# EEZ_DIB_MCU_r1B6.net
KiCad netlist of a schematic drawn in EAGLE
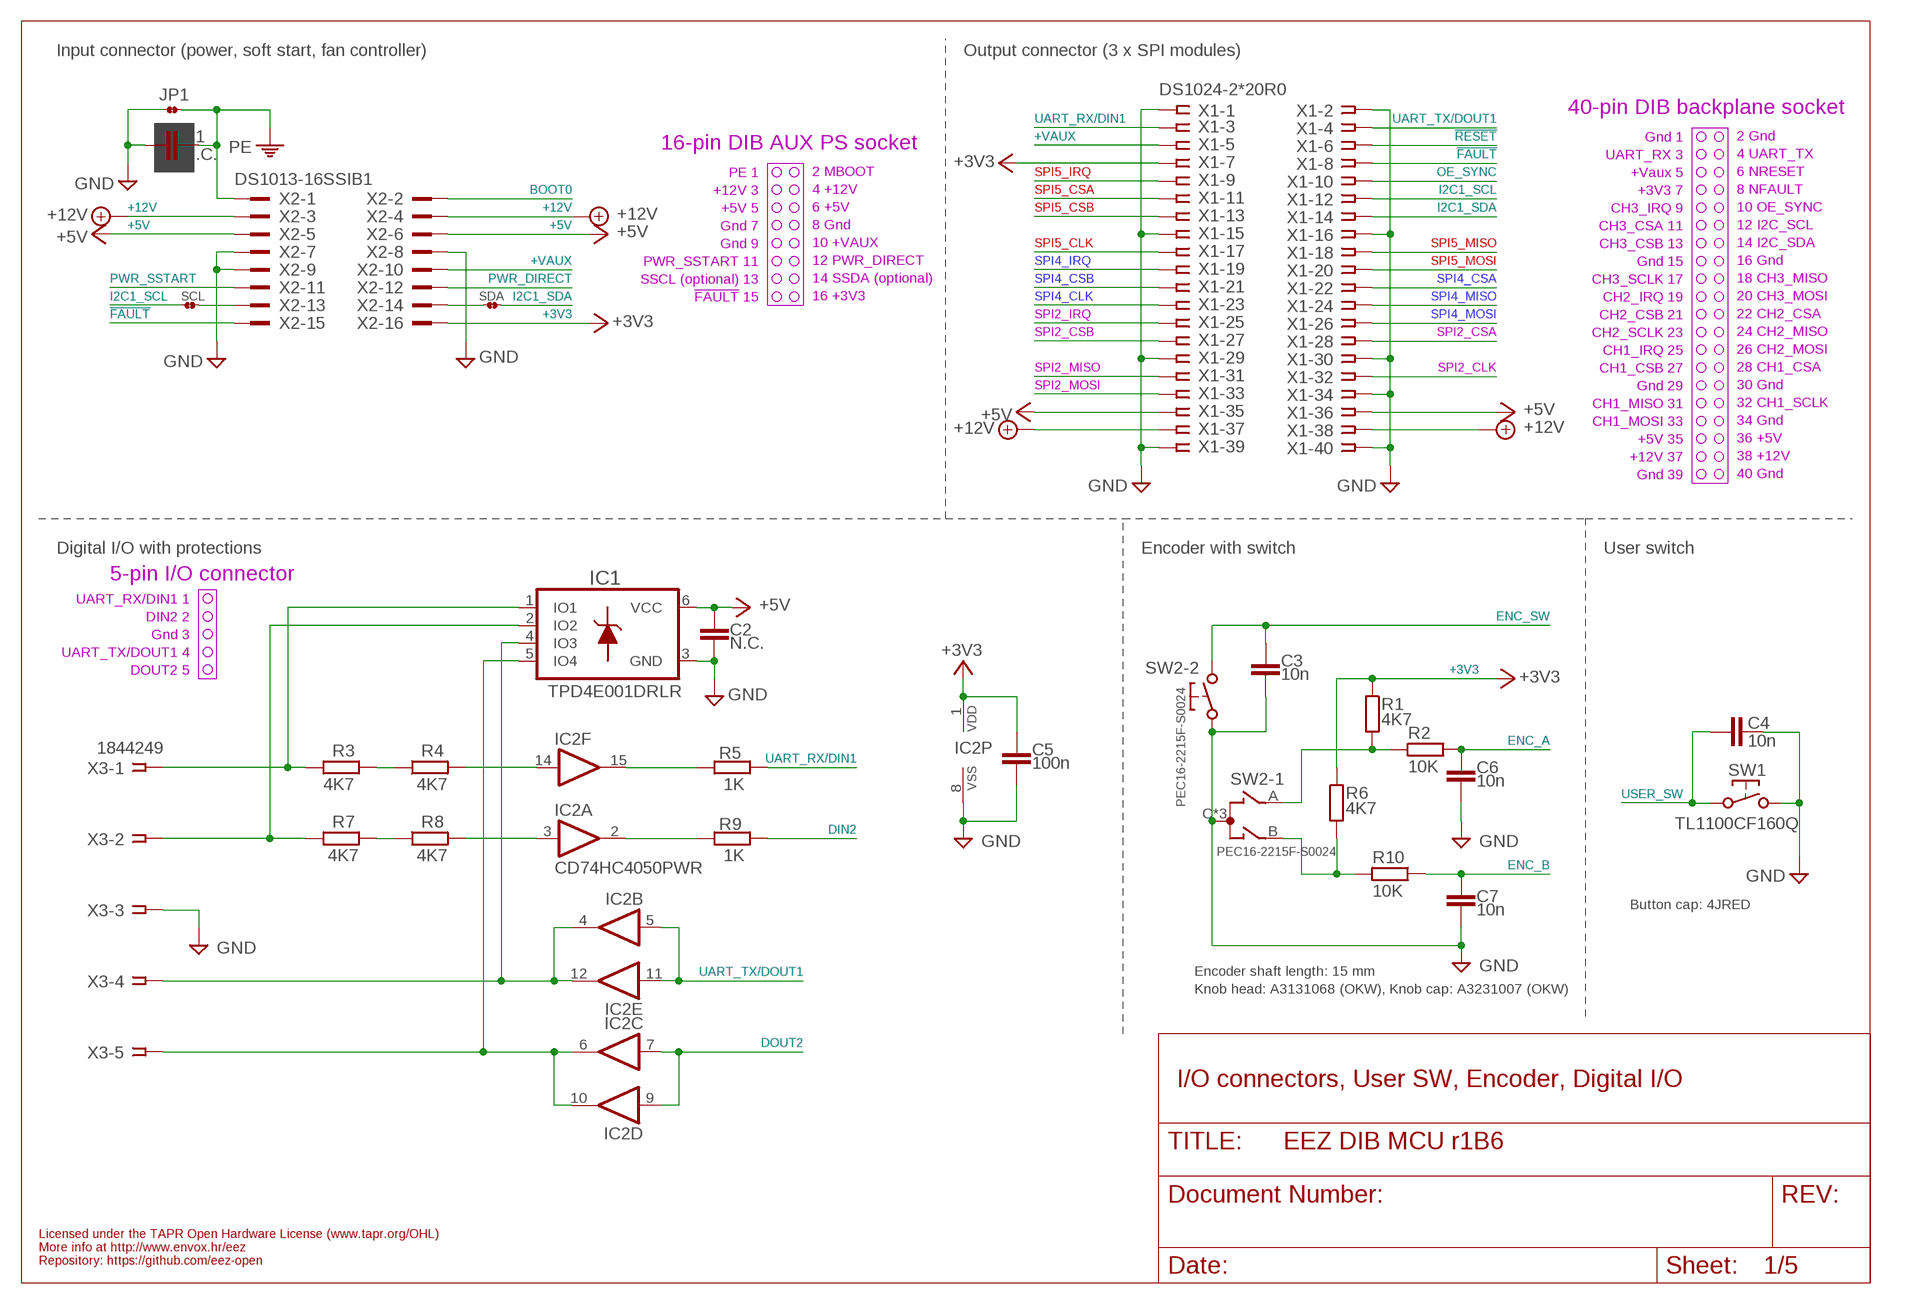
[diagram p0: schematic, sheet 1]
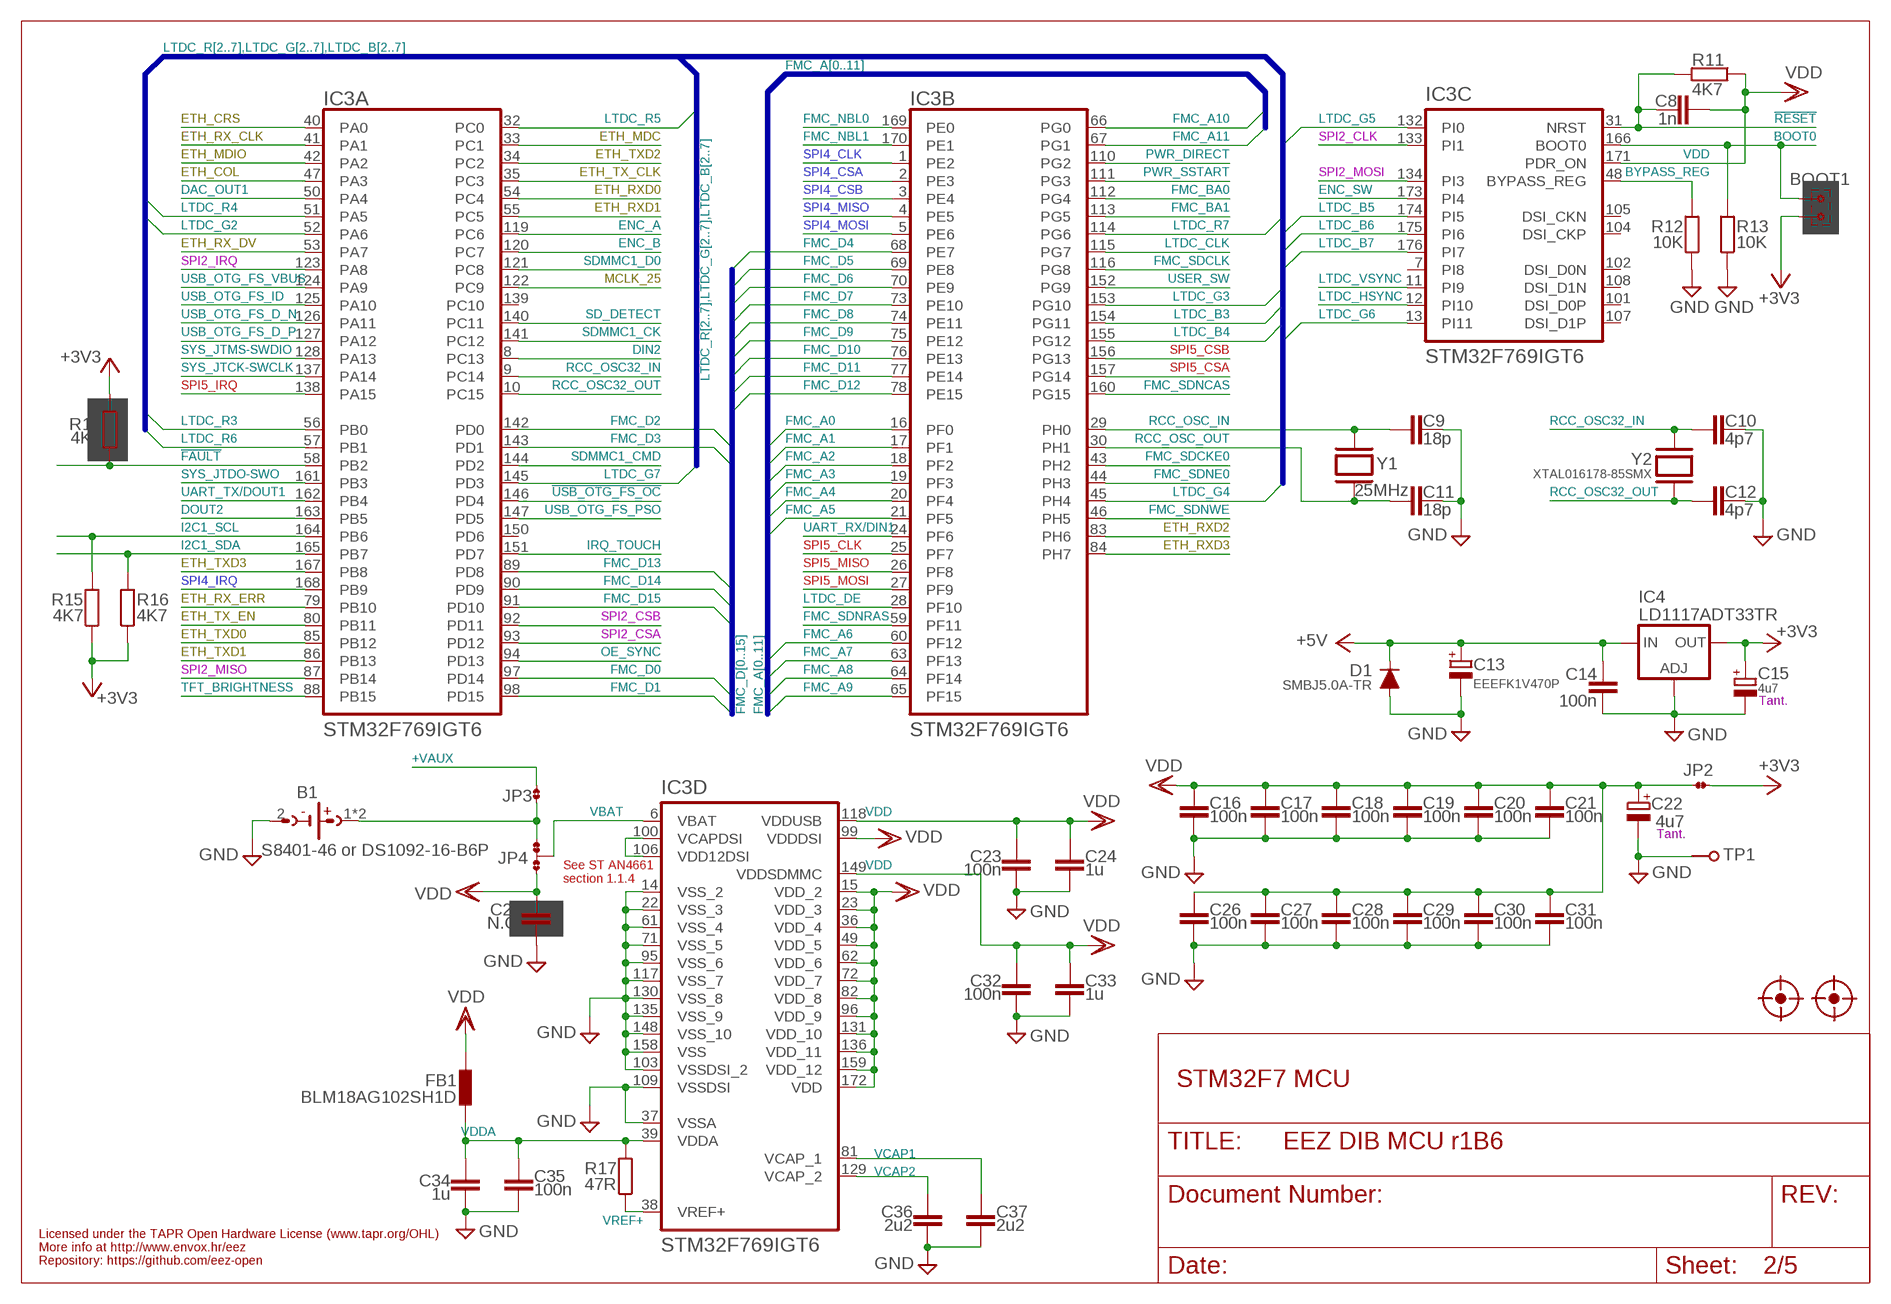
[diagram p1: schematic, sheet 2]
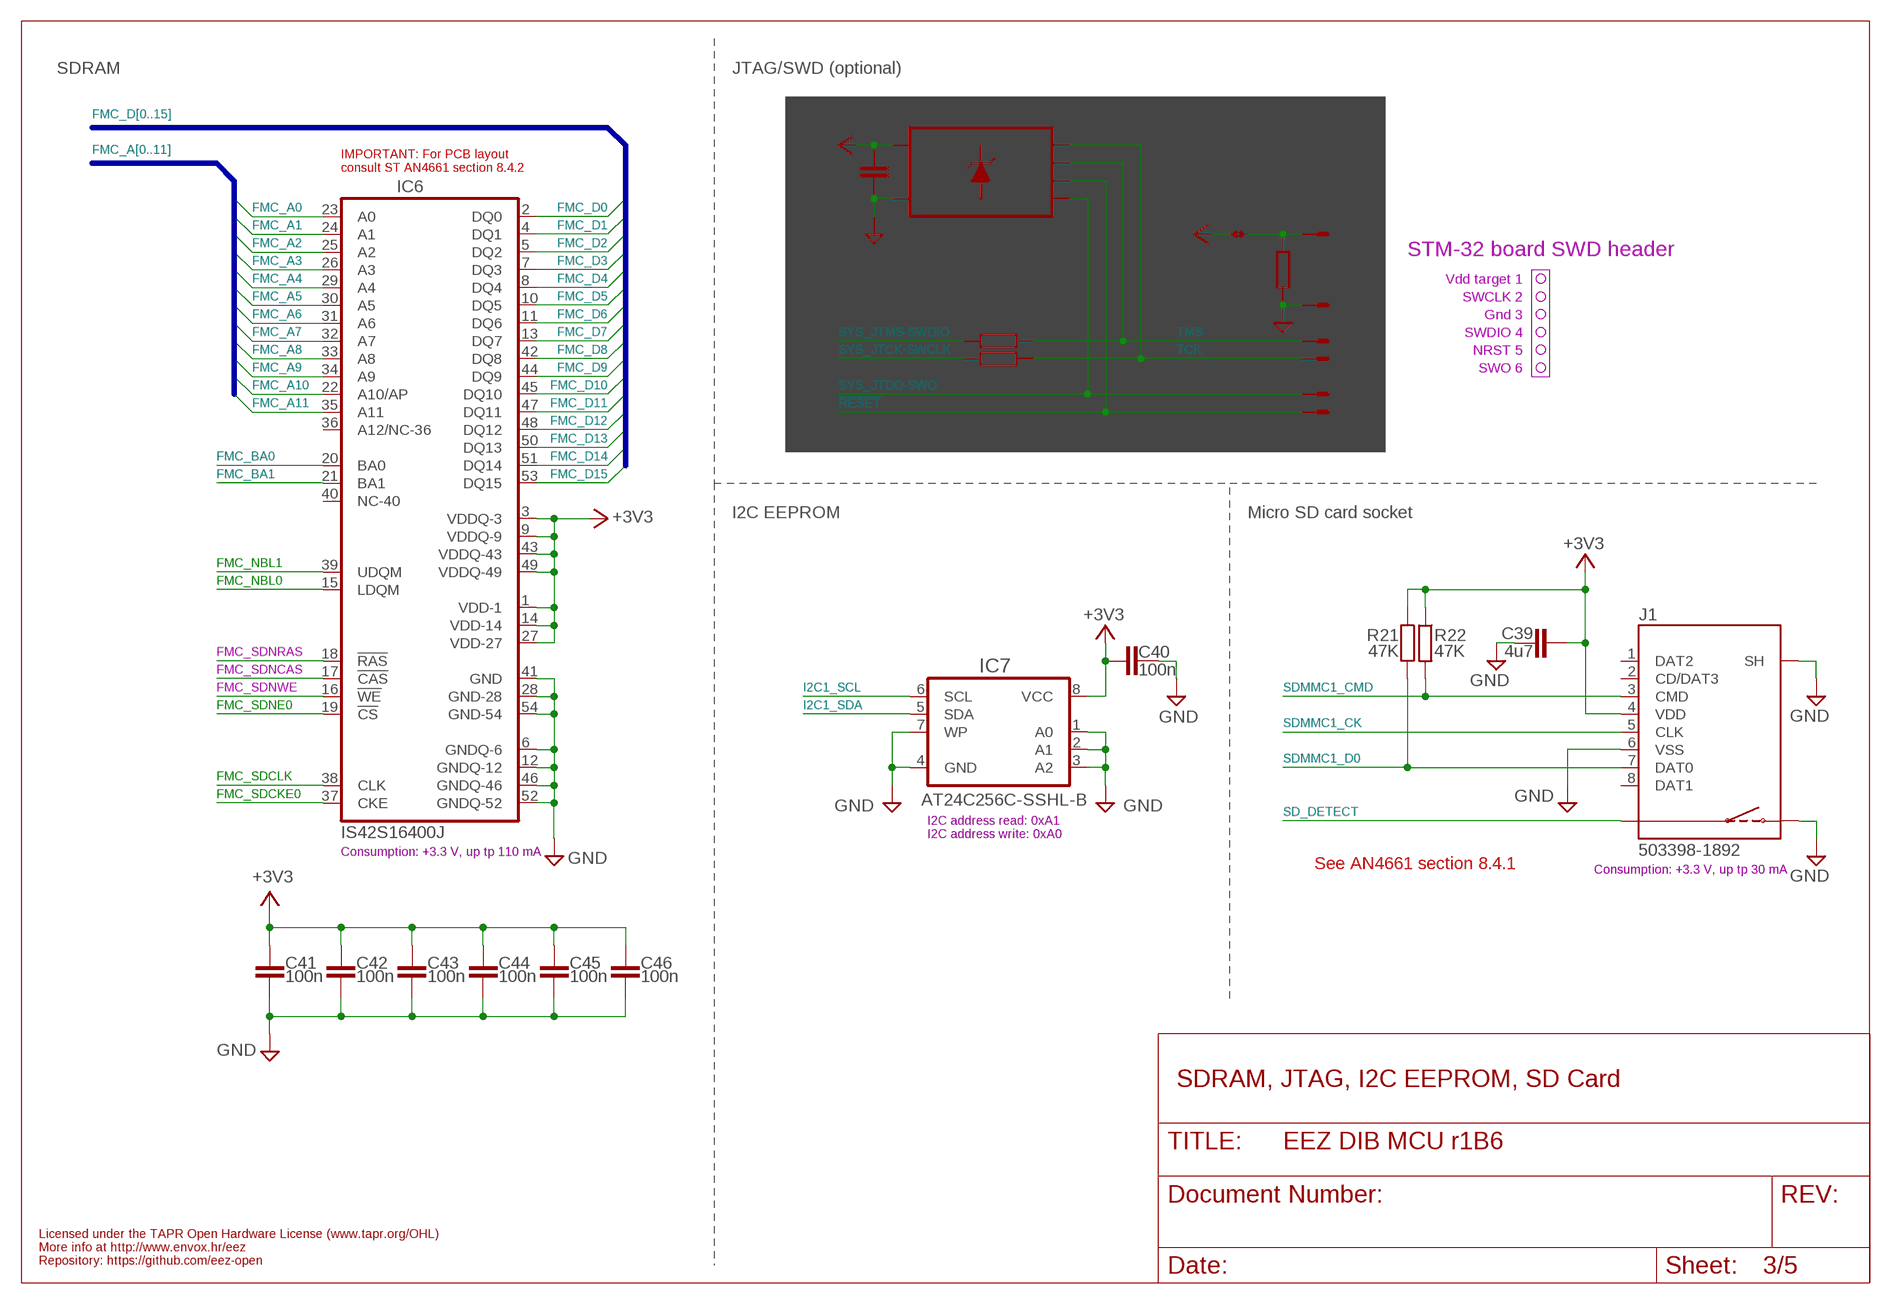
[diagram p2: schematic, sheet 3]
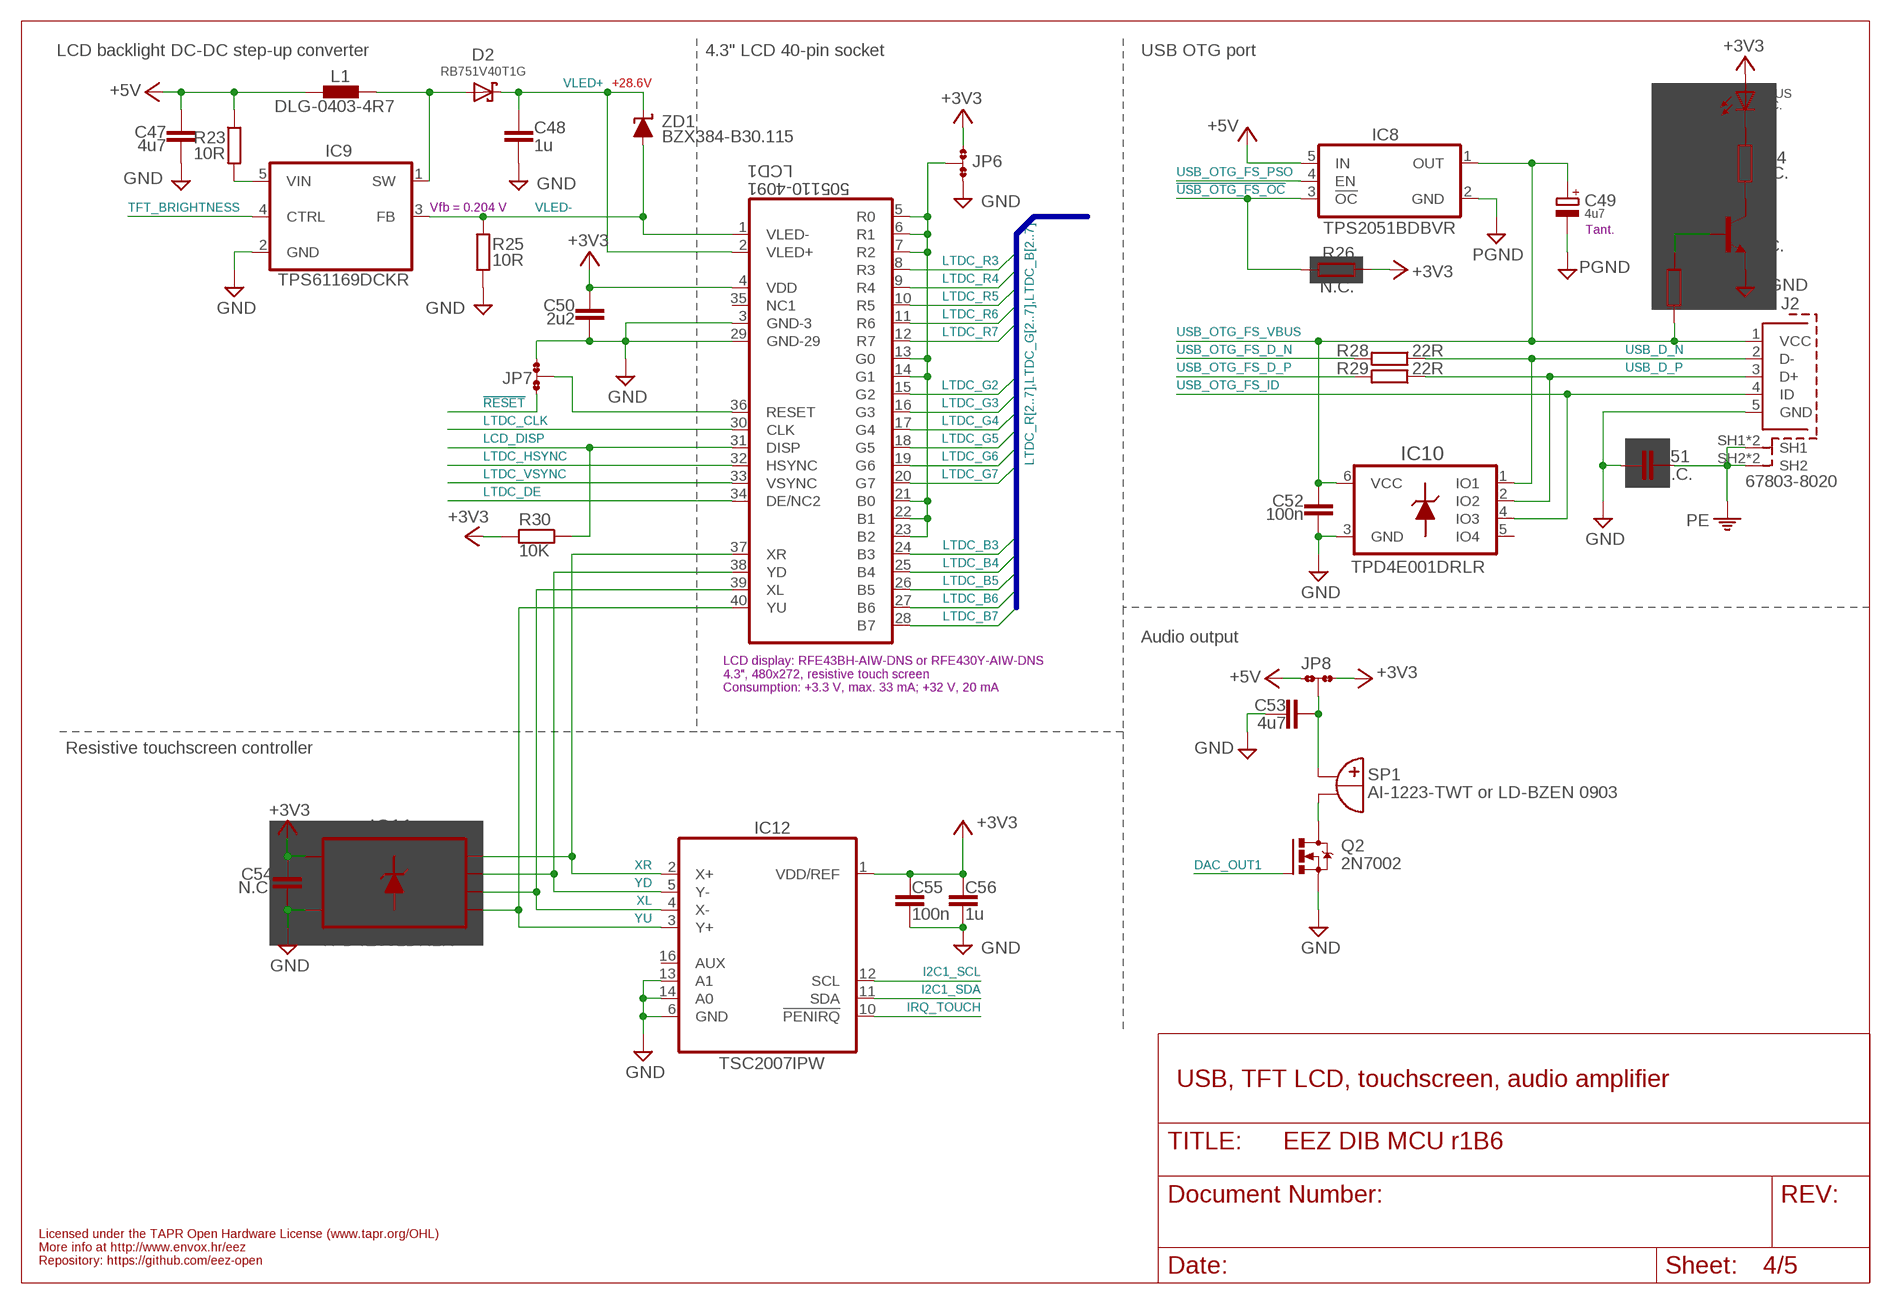
[diagram p3: schematic, sheet 4]
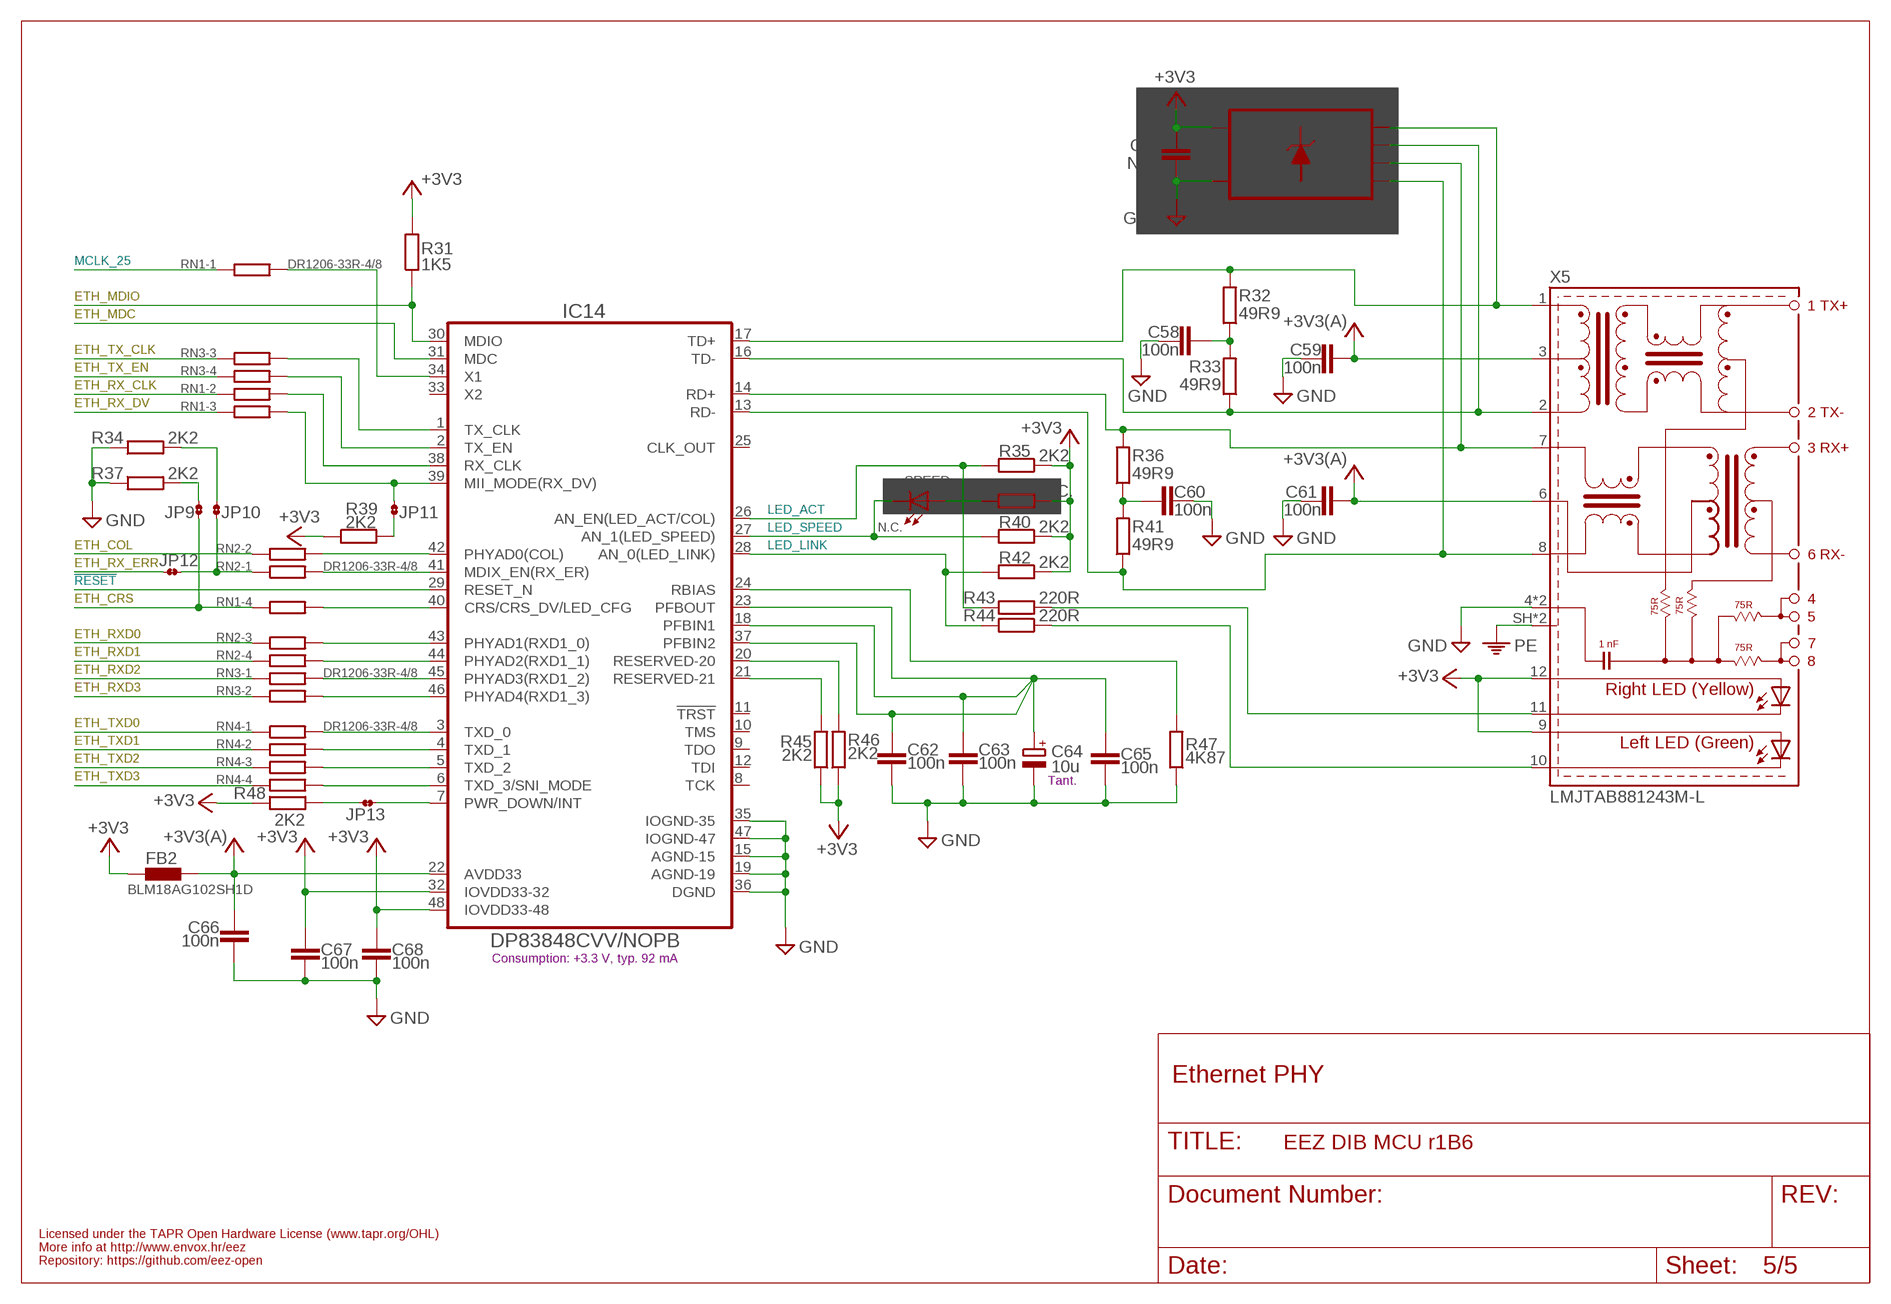
[diagram p4: schematic, sheet 5]

(export (version "E")
  (design (tool "Eeschema 10.0.6"))
  (components
    (comp (ref "B1")
      (value "S8401-46 or DS1092-16-B6P")
      (footprint "eagle-import:S8401-46")
      (libsource (lib "eagle-import") (part "CELL_BATTERYVERT"))
    )
    (comp (ref "BOOT1")
      (value "JUMPER-2PIN-2MM")
      (footprint "eagle-import:2MM-2")
      (libsource (lib "eagle-import") (part "JUMPER-2PIN-2MM"))
    )
    (comp (ref "C8")
      (value "1n")
      (footprint "eagle-import:C0805")
      (libsource (lib "eagle-import") (part "C-EUC0805"))
    )
    (comp (ref "C9")
      (value "18p")
      (footprint "eagle-import:C0603")
      (libsource (lib "eagle-import") (part "C-EUC0603"))
    )
    (comp (ref "C10")
      (value "4p7")
      (footprint "eagle-import:C0603")
      (libsource (lib "eagle-import") (part "C-EUC0603"))
    )
    (comp (ref "C11")
      (value "18p")
      (footprint "eagle-import:C0603")
      (libsource (lib "eagle-import") (part "C-EUC0603"))
    )
    (comp (ref "C12")
      (value "4p7")
      (footprint "eagle-import:C0603")
      (libsource (lib "eagle-import") (part "C-EUC0603"))
    )
    (comp (ref "C13")
      (value "EEEFK1V470P")
      (footprint "eagle-import:CAPAE660X610N")
      (libsource (lib "eagle-import") (part "ECAPPANASONIC_H"))
    )
    (comp (ref "C14")
      (value "100n")
      (footprint "eagle-import:C0603")
      (libsource (lib "eagle-import") (part "C-EUC0603"))
    )
    (comp (ref "C15")
      (value "4u7")
      (footprint "eagle-import:EC1206")
      (libsource (lib "eagle-import") (part "ECAP1206"))
    )
    (comp (ref "C16")
      (value "100n")
      (footprint "eagle-import:C0603")
      (libsource (lib "eagle-import") (part "C-EUC0603"))
    )
    (comp (ref "C17")
      (value "100n")
      (footprint "eagle-import:C0603")
      (libsource (lib "eagle-import") (part "C-EUC0603"))
    )
    (comp (ref "C18")
      (value "100n")
      (footprint "eagle-import:C0603")
      (libsource (lib "eagle-import") (part "C-EUC0603"))
    )
    (comp (ref "C19")
      (value "100n")
      (footprint "eagle-import:C0603")
      (libsource (lib "eagle-import") (part "C-EUC0603"))
    )
    (comp (ref "C20")
      (value "100n")
      (footprint "eagle-import:C0603")
      (libsource (lib "eagle-import") (part "C-EUC0603"))
    )
    (comp (ref "C21")
      (value "100n")
      (footprint "eagle-import:C0603")
      (libsource (lib "eagle-import") (part "C-EUC0603"))
    )
    (comp (ref "C22")
      (value "4u7")
      (footprint "eagle-import:EC1206")
      (libsource (lib "eagle-import") (part "ECAP1206"))
    )
    (comp (ref "C23")
      (value "100n")
      (footprint "eagle-import:C0603")
      (libsource (lib "eagle-import") (part "C-EUC0603"))
    )
    (comp (ref "C24")
      (value "1u")
      (footprint "eagle-import:C0805")
      (libsource (lib "eagle-import") (part "C-EUC0805"))
    )
    (comp (ref "C25")
      (value "N.C.")
      (footprint "eagle-import:C0603")
      (libsource (lib "eagle-import") (part "C-EUC0603"))
    )
    (comp (ref "C26")
      (value "100n")
      (footprint "eagle-import:C0603")
      (libsource (lib "eagle-import") (part "C-EUC0603"))
    )
    (comp (ref "C27")
      (value "100n")
      (footprint "eagle-import:C0603")
      (libsource (lib "eagle-import") (part "C-EUC0603"))
    )
    (comp (ref "C28")
      (value "100n")
      (footprint "eagle-import:C0603")
      (libsource (lib "eagle-import") (part "C-EUC0603"))
    )
    (comp (ref "C29")
      (value "100n")
      (footprint "eagle-import:C0603")
      (libsource (lib "eagle-import") (part "C-EUC0603"))
    )
    (comp (ref "C30")
      (value "100n")
      (footprint "eagle-import:C0603")
      (libsource (lib "eagle-import") (part "C-EUC0603"))
    )
    (comp (ref "C31")
      (value "100n")
      (footprint "eagle-import:C0603")
      (libsource (lib "eagle-import") (part "C-EUC0603"))
    )
    (comp (ref "C32")
      (value "100n")
      (footprint "eagle-import:C0603")
      (libsource (lib "eagle-import") (part "C-EUC0603"))
    )
    (comp (ref "C33")
      (value "1u")
      (footprint "eagle-import:C0805")
      (libsource (lib "eagle-import") (part "C-EUC0805"))
    )
    (comp (ref "C34")
      (value "1u")
      (footprint "eagle-import:C0805")
      (libsource (lib "eagle-import") (part "C-EUC0805"))
    )
    (comp (ref "C35")
      (value "100n")
      (footprint "eagle-import:C0603")
      (libsource (lib "eagle-import") (part "C-EUC0603"))
    )
    (comp (ref "C36")
      (value "2u2")
      (footprint "eagle-import:C0805")
      (libsource (lib "eagle-import") (part "C-EUC0805"))
    )
    (comp (ref "C37")
      (value "2u2")
      (footprint "eagle-import:C0805")
      (libsource (lib "eagle-import") (part "C-EUC0805"))
    )
    (comp (ref "D1")
      (value "SMBJ5.0A-TR")
      (footprint "eagle-import:DO214AA")
      (libsource (lib "eagle-import") (part "DIODEDO214AA"))
    )
    (comp (ref "FB1")
      (value "BLM18AG102SH1D")
      (footprint "eagle-import:BEAD0603")
      (libsource (lib "eagle-import") (part "FERRITE_BEAD0603"))
    )
    (comp (ref "FM1")
      (value "FIDUCIAL")
      (footprint "eagle-import:FIDUCIAL")
      (libsource (lib "eagle-import") (part "FIDUCIAL"))
    )
    (comp (ref "FM2")
      (value "FIDUCIAL")
      (footprint "eagle-import:FIDUCIAL")
      (libsource (lib "eagle-import") (part "FIDUCIAL"))
    )
    (comp (ref "IC3")
      (value "STM32F769IGT6")
      (footprint "eagle-import:LQFP-176_24X24MM")
      (fields
        (field (name "MANUFACTURER_PART_NUMBER") "stm32f769ixt")
        (field (name "COPYRIGHT") "Copyright C 2016 Accelerated Designs. All rights reserved")
      )
      (libsource (lib "eagle-import") (part "STM32F769IXT"))
    )
    (comp (ref "IC4")
      (value "LD1117ADT33TR")
      (footprint "eagle-import:DPACK")
      (libsource (lib "eagle-import") (part "LD117A?DT33TR"))
    )
    (comp (ref "JP2")
      (value "JP2-NOCUT")
      (footprint "eagle-import:JP2-NOCUT")
      (libsource (lib "eagle-import") (part "JP2-NOCUT"))
    )
    (comp (ref "JP3")
      (value "JP2-CUT")
      (footprint "eagle-import:JP2-CUT")
      (libsource (lib "eagle-import") (part "JP2-CUT"))
    )
    (comp (ref "JP4")
      (value "JP3-CUT")
      (footprint "eagle-import:JP3-CUT")
      (libsource (lib "eagle-import") (part "JP3-CUT"))
    )
    (comp (ref "R11")
      (value "4K7")
      (footprint "eagle-import:R0805")
      (libsource (lib "eagle-import") (part "R-EU_R0805"))
    )
    (comp (ref "R12")
      (value "10K")
      (footprint "eagle-import:R0805")
      (libsource (lib "eagle-import") (part "R-EU_R0805"))
    )
    (comp (ref "R13")
      (value "10K")
      (footprint "eagle-import:R0805")
      (libsource (lib "eagle-import") (part "R-EU_R0805"))
    )
    (comp (ref "R14")
      (value "4K7")
      (footprint "eagle-import:R0805")
      (libsource (lib "eagle-import") (part "R-EU_R0805"))
    )
    (comp (ref "R15")
      (value "4K7")
      (footprint "eagle-import:R0805")
      (libsource (lib "eagle-import") (part "R-EU_R0805"))
    )
    (comp (ref "R16")
      (value "4K7")
      (footprint "eagle-import:R0805")
      (libsource (lib "eagle-import") (part "R-EU_R0805"))
    )
    (comp (ref "R17")
      (value "47R")
      (footprint "eagle-import:R0805")
      (libsource (lib "eagle-import") (part "R-EU_R0805"))
    )
    (comp (ref "TP1")
      (value "PCB_TEST_TABSHIELD")
      (footprint "eagle-import:PCB_SHIELD_TAB")
      (libsource (lib "eagle-import") (part "PCB_TEST_TABSHIELD"))
    )
    (comp (ref "Y1")
      (value "25MHz")
      (footprint "eagle-import:HC-49_4H")
      (libsource (lib "eagle-import") (part "XTALSMD"))
    )
    (comp (ref "Y2")
      (value "XTAL016178-85SMX")
      (footprint "eagle-import:85SMX")
      (libsource (lib "eagle-import") (part "XTAL85SMX"))
    )
    (comp (ref "C38")
      (value "N.C.")
      (footprint "eagle-import:C0603")
      (libsource (lib "eagle-import") (part "C-EUC0603"))
    )
    (comp (ref "C39")
      (value "4u7")
      (footprint "eagle-import:C1206")
      (libsource (lib "eagle-import") (part "C-EUC1206"))
    )
    (comp (ref "C40")
      (value "100n")
      (footprint "eagle-import:C0603")
      (libsource (lib "eagle-import") (part "C-EUC0603"))
    )
    (comp (ref "C41")
      (value "100n")
      (footprint "eagle-import:C0603")
      (libsource (lib "eagle-import") (part "C-EUC0603"))
    )
    (comp (ref "C42")
      (value "100n")
      (footprint "eagle-import:C0603")
      (libsource (lib "eagle-import") (part "C-EUC0603"))
    )
    (comp (ref "C43")
      (value "100n")
      (footprint "eagle-import:C0603")
      (libsource (lib "eagle-import") (part "C-EUC0603"))
    )
    (comp (ref "C44")
      (value "100n")
      (footprint "eagle-import:C0603")
      (libsource (lib "eagle-import") (part "C-EUC0603"))
    )
    (comp (ref "C45")
      (value "100n")
      (footprint "eagle-import:C0603")
      (libsource (lib "eagle-import") (part "C-EUC0603"))
    )
    (comp (ref "C46")
      (value "100n")
      (footprint "eagle-import:C0603")
      (libsource (lib "eagle-import") (part "C-EUC0603"))
    )
    (comp (ref "IC5")
      (value "TPD4E001DRLR")
      (footprint "eagle-import:DRL6")
      (libsource (lib "eagle-import") (part "TPD4E001-DRL"))
    )
    (comp (ref "IC6")
      (value "IS42S16400J")
      (footprint "eagle-import:TSOPII-54")
      (libsource (lib "eagle-import") (part "IS42S16400"))
    )
    (comp (ref "IC7")
      (value "AT24C256C-SSHL-B")
      (footprint "eagle-import:SOIC127P600X173-8N")
      (libsource (lib "eagle-import") (part "AT24CXXSOIC8"))
    )
    (comp (ref "J1")
      (value "503398-1892")
      (footprint "eagle-import:5033981892")
      (libsource (lib "eagle-import") (part "5033981892"))
    )
    (comp (ref "JP5")
      (value "JP2-CUT")
      (footprint "eagle-import:JP2-CUT")
      (libsource (lib "eagle-import") (part "JP2-CUT"))
    )
    (comp (ref "R18")
      (value "N.C.")
      (footprint "eagle-import:R0805")
      (libsource (lib "eagle-import") (part "R-EU_R0805"))
    )
    (comp (ref "R19")
      (value "N.C.")
      (footprint "eagle-import:R0805")
      (libsource (lib "eagle-import") (part "R-EU_R0805"))
    )
    (comp (ref "R20")
      (value "N.C.")
      (footprint "eagle-import:R0805")
      (libsource (lib "eagle-import") (part "R-EU_R0805"))
    )
    (comp (ref "R21")
      (value "47K")
      (footprint "eagle-import:R0805")
      (libsource (lib "eagle-import") (part "R-EU_R0805"))
    )
    (comp (ref "R22")
      (value "47K")
      (footprint "eagle-import:R0805")
      (libsource (lib "eagle-import") (part "R-EU_R0805"))
    )
    (comp (ref "X4")
      (value "N.C.")
      (footprint "eagle-import:22-23-2061")
      (fields (field (name "MF") "MOLEX") (field (name "MPN") "22-23-2061"))
      (libsource (lib "eagle-import") (part "22-23-2061"))
    )
    (comp (ref "C47")
      (value "4u7")
      (footprint "eagle-import:C1206")
      (libsource (lib "eagle-import") (part "C-EUC1206"))
    )
    (comp (ref "C48")
      (value "1u")
      (footprint "eagle-import:C0805")
      (libsource (lib "eagle-import") (part "C-EUC0805"))
    )
    (comp (ref "C49")
      (value "4u7")
      (footprint "eagle-import:EC1206")
      (libsource (lib "eagle-import") (part "ECAP1206"))
    )
    (comp (ref "C50")
      (value "2u2")
      (footprint "eagle-import:C0805")
      (libsource (lib "eagle-import") (part "C-EUC0805"))
    )
    (comp (ref "C51")
      (value "N.C.")
      (footprint "eagle-import:C0805")
      (libsource (lib "eagle-import") (part "C-EUC0805"))
    )
    (comp (ref "C52")
      (value "100n")
      (footprint "eagle-import:C0603")
      (libsource (lib "eagle-import") (part "C-EUC0603"))
    )
    (comp (ref "C53")
      (value "4u7")
      (footprint "eagle-import:C1206")
      (libsource (lib "eagle-import") (part "C-EUC1206"))
    )
    (comp (ref "C54")
      (value "N.C.")
      (footprint "eagle-import:C0603")
      (libsource (lib "eagle-import") (part "C-EUC0603"))
    )
    (comp (ref "C55")
      (value "100n")
      (footprint "eagle-import:C0603")
      (libsource (lib "eagle-import") (part "C-EUC0603"))
    )
    (comp (ref "C56")
      (value "1u")
      (footprint "eagle-import:C0805")
      (libsource (lib "eagle-import") (part "C-EUC0805"))
    )
    (comp (ref "D2")
      (value "RB751V40T1G")
      (footprint "eagle-import:SOD323-R")
      (libsource (lib "eagle-import") (part "SCHOTTKYSOD-323R"))
    )
    (comp (ref "IC8")
      (value "TPS2051BDBVR")
      (footprint "eagle-import:DBV5")
      (libsource (lib "eagle-import") (part "TPS2051B"))
    )
    (comp (ref "IC9")
      (value "TPS61169DCKR")
      (footprint "eagle-import:DCK5")
      (fields (field (name "MANUFACTURER") "Texas Instruments"))
      (libsource (lib "eagle-import") (part "TPS61169DCKR"))
    )
    (comp (ref "IC10")
      (value "TPD4E001DRLR")
      (footprint "eagle-import:DRL6")
      (libsource (lib "eagle-import") (part "TPD4E001-DRL"))
    )
    (comp (ref "IC11")
      (value "TPD4E001DRLR")
      (footprint "eagle-import:DRL6")
      (libsource (lib "eagle-import") (part "TPD4E001-DRL"))
    )
    (comp (ref "IC12")
      (value "TSC2007IPW")
      (footprint "eagle-import:PW(R-PDSO-G16)")
      (libsource (lib "eagle-import") (part "TSC2007IPW"))
    )
    (comp (ref "J2")
      (value "67803-8020")
      (footprint "eagle-import:678038020")
      (libsource (lib "eagle-import") (part "678038020"))
    )
    (comp (ref "JP6")
      (value "JP3-CUT")
      (footprint "eagle-import:JP3-CUT")
      (libsource (lib "eagle-import") (part "JP3-CUT"))
    )
    (comp (ref "JP7")
      (value "JP3-CUT")
      (footprint "eagle-import:JP3-CUT")
      (libsource (lib "eagle-import") (part "JP3-CUT"))
    )
    (comp (ref "JP8")
      (value "JP3-CUT")
      (footprint "eagle-import:JP3-CUT")
      (libsource (lib "eagle-import") (part "JP3-CUT"))
    )
    (comp (ref "L1")
      (value "DLG-0403-4R7")
      (footprint "eagle-import:DE0403")
      (libsource (lib "eagle-import") (part "DE0403"))
    )
    (comp (ref "LCD1")
      (value "505110-4091")
      (footprint "eagle-import:FPC_40")
      (libsource (lib "eagle-import") (part "RFE430Y-AIW-DNS"))
    )
    (comp (ref "Q1")
      (value "N.C.")
      (footprint "eagle-import:SOT23-BEC")
      (libsource (lib "eagle-import") (part "-NPN-SOT23-BECMMBT5551LT1"))
    )
    (comp (ref "Q2")
      (value "2N7002")
      (footprint "eagle-import:SOT103P240X110-3N")
      (fields (field (name "MPN") "2N7002-7-F"))
      (libsource (lib "eagle-import") (part "2N7002"))
    )
    (comp (ref "R23")
      (value "10R")
      (footprint "eagle-import:R0805")
      (libsource (lib "eagle-import") (part "R-EU_R0805"))
    )
    (comp (ref "R24")
      (value "N.C.")
      (footprint "eagle-import:R0805")
      (libsource (lib "eagle-import") (part "R-EU_R0805"))
    )
    (comp (ref "R25")
      (value "10R")
      (footprint "eagle-import:R0805")
      (libsource (lib "eagle-import") (part "R-EU_R0805"))
    )
    (comp (ref "R26")
      (value "N.C.")
      (footprint "eagle-import:R0805")
      (libsource (lib "eagle-import") (part "R-EU_R0805"))
    )
    (comp (ref "R27")
      (value "N.C.")
      (footprint "eagle-import:R0805")
      (libsource (lib "eagle-import") (part "R-EU_R0805"))
    )
    (comp (ref "R28")
      (value "22R")
      (footprint "eagle-import:R0805")
      (libsource (lib "eagle-import") (part "R-EU_R0805"))
    )
    (comp (ref "R29")
      (value "22R")
      (footprint "eagle-import:R0805")
      (libsource (lib "eagle-import") (part "R-EU_R0805"))
    )
    (comp (ref "R30")
      (value "10K")
      (footprint "eagle-import:R0805")
      (libsource (lib "eagle-import") (part "R-EU_R0805"))
    )
    (comp (ref "SP1")
      (value "AI-1223-TWT or LD-BZEN 0903")
      (footprint "eagle-import:AI-1223-TWT_COMBO")
      (libsource (lib "eagle-import") (part "AI-1223-TWT-LDB0903"))
    )
    (comp (ref "VBUS")
      (value "N.C.")
      (footprint "eagle-import:LED_0805")
      (libsource (lib "eagle-import") (part "LED0805"))
    )
    (comp (ref "ZD1")
      (value "BZX384-B30.115")
      (footprint "eagle-import:SOD323-W")
      (libsource (lib "eagle-import") (part "ZENER-DIODESOD323"))
    )
    (comp (ref "C57")
      (value "N.C.")
      (footprint "eagle-import:C0603")
      (libsource (lib "eagle-import") (part "C-EUC0603"))
    )
    (comp (ref "C58")
      (value "100n")
      (footprint "eagle-import:C0603")
      (libsource (lib "eagle-import") (part "C-EUC0603"))
    )
    (comp (ref "C59")
      (value "100n")
      (footprint "eagle-import:C0603")
      (libsource (lib "eagle-import") (part "C-EUC0603"))
    )
    (comp (ref "C60")
      (value "100n")
      (footprint "eagle-import:C0603")
      (libsource (lib "eagle-import") (part "C-EUC0603"))
    )
    (comp (ref "C61")
      (value "100n")
      (footprint "eagle-import:C0603")
      (libsource (lib "eagle-import") (part "C-EUC0603"))
    )
    (comp (ref "C62")
      (value "100n")
      (footprint "eagle-import:C0603")
      (libsource (lib "eagle-import") (part "C-EUC0603"))
    )
    (comp (ref "C63")
      (value "100n")
      (footprint "eagle-import:C0603")
      (libsource (lib "eagle-import") (part "C-EUC0603"))
    )
    (comp (ref "C64")
      (value "10u")
      (footprint "eagle-import:EC1206")
      (libsource (lib "eagle-import") (part "ECAP1206"))
    )
    (comp (ref "C65")
      (value "100n")
      (footprint "eagle-import:C0603")
      (libsource (lib "eagle-import") (part "C-EUC0603"))
    )
    (comp (ref "C66")
      (value "100n")
      (footprint "eagle-import:C0603")
      (libsource (lib "eagle-import") (part "C-EUC0603"))
    )
    (comp (ref "C67")
      (value "100n")
      (footprint "eagle-import:C0603")
      (libsource (lib "eagle-import") (part "C-EUC0603"))
    )
    (comp (ref "C68")
      (value "100n")
      (footprint "eagle-import:C0603")
      (libsource (lib "eagle-import") (part "C-EUC0603"))
    )
    (comp (ref "FB2")
      (value "BLM18AG102SH1D")
      (footprint "eagle-import:BEAD0603")
      (libsource (lib "eagle-import") (part "FERRITE_BEAD0603"))
    )
    (comp (ref "IC13")
      (value "TPD4E001DRLR")
      (footprint "eagle-import:DRL6")
      (libsource (lib "eagle-import") (part "TPD4E001-DRL"))
    )
    (comp (ref "IC14")
      (value "DP83848CVV/NOPB")
      (footprint "eagle-import:PT48")
      (libsource (lib "eagle-import") (part "DP83848CVV/NOPB"))
    )
    (comp (ref "JP9")
      (value "JP2-CUT")
      (footprint "eagle-import:JP2-CUT")
      (libsource (lib "eagle-import") (part "JP2-CUT"))
    )
    (comp (ref "JP10")
      (value "JP2-CUT")
      (footprint "eagle-import:JP2-CUT")
      (libsource (lib "eagle-import") (part "JP2-CUT"))
    )
    (comp (ref "JP11")
      (value "JP2-CUT")
      (footprint "eagle-import:JP2-CUT")
      (libsource (lib "eagle-import") (part "JP2-CUT"))
    )
    (comp (ref "JP12")
      (value "JP2-NOCUT")
      (footprint "eagle-import:JP2-NOCUT")
      (libsource (lib "eagle-import") (part "JP2-NOCUT"))
    )
    (comp (ref "JP13")
      (value "JP2-NOCUT")
      (footprint "eagle-import:JP2-NOCUT")
      (libsource (lib "eagle-import") (part "JP2-NOCUT"))
    )
    (comp (ref "R31")
      (value "1K5")
      (footprint "eagle-import:R0805")
      (libsource (lib "eagle-import") (part "R-EU_R0805"))
    )
    (comp (ref "R32")
      (value "49R9")
      (footprint "eagle-import:R0805")
      (libsource (lib "eagle-import") (part "R-EU_R0805"))
    )
    (comp (ref "R33")
      (value "49R9")
      (footprint "eagle-import:R0805")
      (libsource (lib "eagle-import") (part "R-EU_R0805"))
    )
    (comp (ref "R34")
      (value "2K2")
      (footprint "eagle-import:R0805")
      (libsource (lib "eagle-import") (part "R-EU_R0805"))
    )
    (comp (ref "R35")
      (value "2K2")
      (footprint "eagle-import:R0805")
      (libsource (lib "eagle-import") (part "R-EU_R0805"))
    )
    (comp (ref "R36")
      (value "49R9")
      (footprint "eagle-import:R0805")
      (libsource (lib "eagle-import") (part "R-EU_R0805"))
    )
    (comp (ref "R37")
      (value "2K2")
      (footprint "eagle-import:R0805")
      (libsource (lib "eagle-import") (part "R-EU_R0805"))
    )
    (comp (ref "R38")
      (value "N.C.")
      (footprint "eagle-import:R0805")
      (libsource (lib "eagle-import") (part "R-EU_R0805"))
    )
    (comp (ref "R39")
      (value "2K2")
      (footprint "eagle-import:R0805")
      (libsource (lib "eagle-import") (part "R-EU_R0805"))
    )
    (comp (ref "R40")
      (value "2K2")
      (footprint "eagle-import:R0805")
      (libsource (lib "eagle-import") (part "R-EU_R0805"))
    )
    (comp (ref "R41")
      (value "49R9")
      (footprint "eagle-import:R0805")
      (libsource (lib "eagle-import") (part "R-EU_R0805"))
    )
    (comp (ref "R42")
      (value "2K2")
      (footprint "eagle-import:R0805")
      (libsource (lib "eagle-import") (part "R-EU_R0805"))
    )
    (comp (ref "R43")
      (value "220R")
      (footprint "eagle-import:R0805")
      (libsource (lib "eagle-import") (part "R-EU_R0805"))
    )
    (comp (ref "R44")
      (value "220R")
      (footprint "eagle-import:R0805")
      (libsource (lib "eagle-import") (part "R-EU_R0805"))
    )
    (comp (ref "R45")
      (value "2K2")
      (footprint "eagle-import:R0805")
      (libsource (lib "eagle-import") (part "R-EU_R0805"))
    )
    (comp (ref "R46")
      (value "2K2")
      (footprint "eagle-import:R0805")
      (libsource (lib "eagle-import") (part "R-EU_R0805"))
    )
    (comp (ref "R47")
      (value "4K87")
      (footprint "eagle-import:R0805")
      (libsource (lib "eagle-import") (part "R-EU_R0805"))
    )
    (comp (ref "R48")
      (value "2K2")
      (footprint "eagle-import:R0805")
      (libsource (lib "eagle-import") (part "R-EU_R0805"))
    )
    (comp (ref "RN1")
      (value "DR1206-33R-4/8")
      (footprint "eagle-import:CAY16")
      (libsource (lib "eagle-import") (part "R_ARRAY4"))
    )
    (comp (ref "RN2")
      (value "DR1206-33R-4/8")
      (footprint "eagle-import:CAY16")
      (libsource (lib "eagle-import") (part "R_ARRAY4"))
    )
    (comp (ref "RN3")
      (value "DR1206-33R-4/8")
      (footprint "eagle-import:CAY16")
      (libsource (lib "eagle-import") (part "R_ARRAY4"))
    )
    (comp (ref "RN4")
      (value "DR1206-33R-4/8")
      (footprint "eagle-import:CAY16")
      (libsource (lib "eagle-import") (part "R_ARRAY4"))
    )
    (comp (ref "SPEED")
      (value "N.C.")
      (footprint "eagle-import:LED_0805")
      (libsource (lib "eagle-import") (part "LED0805"))
    )
    (comp (ref "X5")
      (value "LMJTAB881243M-L")
      (footprint "eagle-import:RJ45-TRAFO-LED")
      (libsource (lib "eagle-import") (part "RJ45-TRAFO-LED"))
    )
    (comp (ref "C1")
      (value "N.C.")
      (footprint "eagle-import:C0805")
      (libsource (lib "eagle-import") (part "C-EUC0805"))
    )
    (comp (ref "C2")
      (value "N.C.")
      (footprint "eagle-import:C0603")
      (libsource (lib "eagle-import") (part "C-EUC0603"))
    )
    (comp (ref "C3")
      (value "10n")
      (footprint "eagle-import:C0805")
      (libsource (lib "eagle-import") (part "C-EUC0805"))
    )
    (comp (ref "C4")
      (value "10n")
      (footprint "eagle-import:C0805")
      (libsource (lib "eagle-import") (part "C-EUC0805"))
    )
    (comp (ref "C5")
      (value "100n")
      (footprint "eagle-import:C0603")
      (libsource (lib "eagle-import") (part "C-EUC0603"))
    )
    (comp (ref "C6")
      (value "10n")
      (footprint "eagle-import:C0805")
      (libsource (lib "eagle-import") (part "C-EUC0805"))
    )
    (comp (ref "C7")
      (value "10n")
      (footprint "eagle-import:C0805")
      (libsource (lib "eagle-import") (part "C-EUC0805"))
    )
    (comp (ref "IC1")
      (value "TPD4E001DRLR")
      (footprint "eagle-import:DRL6")
      (libsource (lib "eagle-import") (part "TPD4E001-DRL"))
    )
    (comp (ref "IC2")
      (value "CD74HC4050PWR")
      (footprint "eagle-import:PW16")
      (libsource (lib "eagle-import") (part "CD74HC4050PWR"))
    )
    (comp (ref "JP1")
      (value "JP2-NOCUT")
      (footprint "eagle-import:JP2-NOCUT")
      (libsource (lib "eagle-import") (part "JP2-NOCUT"))
    )
    (comp (ref "R1")
      (value "4K7")
      (footprint "eagle-import:R0805")
      (libsource (lib "eagle-import") (part "R-EU_R0805"))
    )
    (comp (ref "R2")
      (value "10K")
      (footprint "eagle-import:R0805")
      (libsource (lib "eagle-import") (part "R-EU_R0805"))
    )
    (comp (ref "R3")
      (value "4K7")
      (footprint "eagle-import:R0805")
      (libsource (lib "eagle-import") (part "R-EU_R0805"))
    )
    (comp (ref "R4")
      (value "4K7")
      (footprint "eagle-import:R0805")
      (libsource (lib "eagle-import") (part "R-EU_R0805"))
    )
    (comp (ref "R5")
      (value "1K")
      (footprint "eagle-import:R0805")
      (libsource (lib "eagle-import") (part "R-EU_R0805"))
    )
    (comp (ref "R6")
      (value "4K7")
      (footprint "eagle-import:R0805")
      (libsource (lib "eagle-import") (part "R-EU_R0805"))
    )
    (comp (ref "R7")
      (value "4K7")
      (footprint "eagle-import:R0805")
      (libsource (lib "eagle-import") (part "R-EU_R0805"))
    )
    (comp (ref "R8")
      (value "4K7")
      (footprint "eagle-import:R0805")
      (libsource (lib "eagle-import") (part "R-EU_R0805"))
    )
    (comp (ref "R9")
      (value "1K")
      (footprint "eagle-import:R0805")
      (libsource (lib "eagle-import") (part "R-EU_R0805"))
    )
    (comp (ref "R10")
      (value "10K")
      (footprint "eagle-import:R0805")
      (libsource (lib "eagle-import") (part "R-EU_R0805"))
    )
    (comp (ref "SCL")
      (value "JP2-NOCUT")
      (footprint "eagle-import:JP2-NOCUT")
      (libsource (lib "eagle-import") (part "JP2-NOCUT"))
    )
    (comp (ref "SDA")
      (value "JP2-NOCUT")
      (footprint "eagle-import:JP2-NOCUT")
      (libsource (lib "eagle-import") (part "JP2-NOCUT"))
    )
    (comp (ref "SW1")
      (value "TL1100CF160Q")
      (footprint "eagle-import:TL1100C")
      (libsource (lib "eagle-import") (part "TL1100C"))
    )
    (comp (ref "SW2")
      (value "PEC16-2215F-S0024")
      (footprint "eagle-import:PEC16-2215F")
      (libsource (lib "eagle-import") (part "ENCODER_SW-PEC16"))
    )
    (comp (ref "X1")
      (value "DS1024-2*20R0")
      (footprint "eagle-import:ZL263-40DG")
      (libsource (lib "eagle-import") (part "ZL263-40DG"))
    )
    (comp (ref "X2")
      (value "DS1013-16SSIB1")
      (footprint "eagle-import:IDC-16PIN")
      (libsource (lib "eagle-import") (part "IDC-16PIN"))
    )
    (comp (ref "X3")
      (value "1844249")
      (footprint "eagle-import:MC1,5_5-G-3,5")
      (libsource (lib "eagle-import") (part "MC1,5/5-G-3,5"))
    )
  )
  (nets
    (net (code "1") (name "+3V3") (class "Default")
      (node (ref "BOOT1") (pin "2") (pinfunction "2_2") (pintype "passive"))
      (node (ref "C15") (pin "+") (pinfunction "+_+") (pintype "passive"))
      (node (ref "C38") (pin "1") (pinfunction "1_1") (pintype "passive"))
      (node (ref "C39") (pin "1") (pinfunction "1_1") (pintype "passive"))
      (node (ref "C40") (pin "2") (pinfunction "2_2") (pintype "passive"))
      (node (ref "C41") (pin "1") (pinfunction "1_1") (pintype "passive"))
      (node (ref "C42") (pin "1") (pinfunction "1_1") (pintype "passive"))
      (node (ref "C43") (pin "1") (pinfunction "1_1") (pintype "passive"))
      (node (ref "C44") (pin "1") (pinfunction "1_1") (pintype "passive"))
      (node (ref "C45") (pin "1") (pinfunction "1_1") (pintype "passive"))
      (node (ref "C46") (pin "1") (pinfunction "1_1") (pintype "passive"))
      (node (ref "C5") (pin "1") (pinfunction "1_1") (pintype "passive"))
      (node (ref "C50") (pin "1") (pinfunction "1_1") (pintype "passive"))
      (node (ref "C54") (pin "2") (pinfunction "2_2") (pintype "passive"))
      (node (ref "C55") (pin "2") (pinfunction "2_2") (pintype "passive"))
      (node (ref "C56") (pin "2") (pinfunction "2_2") (pintype "passive"))
      (node (ref "C57") (pin "1") (pinfunction "1_1") (pintype "passive"))
      (node (ref "C67") (pin "1") (pinfunction "1_1") (pintype "passive"))
      (node (ref "C68") (pin "1") (pinfunction "1_1") (pintype "passive"))
      (node (ref "FB2") (pin "P$1") (pinfunction "1_P$1") (pintype "passive"))
      (node (ref "IC11") (pin "6") (pinfunction "VCC_6") (pintype "passive"))
      (node (ref "IC12") (pin "1") (pinfunction "VDD/REF_1") (pintype "passive"))
      (node (ref "IC13") (pin "6") (pinfunction "VCC_6") (pintype "passive"))
      (node (ref "IC14") (pin "32") (pinfunction "IOVDD33-32_32") (pintype "power_in"))
      (node (ref "IC14") (pin "48") (pinfunction "IOVDD33-48_48") (pintype "power_in"))
      (node (ref "IC2") (pin "1") (pinfunction "VDD_1") (pintype "power_in"))
      (node (ref "IC4") (pin "4") (pinfunction "OUT_4") (pintype "passive"))
      (node (ref "IC5") (pin "6") (pinfunction "VCC_6") (pintype "passive"))
      (node (ref "IC6") (pin "1") (pinfunction "VDD-1_1") (pintype "power_in"))
      (node (ref "IC6") (pin "14") (pinfunction "VDD-14_14") (pintype "power_in"))
      (node (ref "IC6") (pin "27") (pinfunction "VDD-27_27") (pintype "power_in"))
      (node (ref "IC6") (pin "3") (pinfunction "VDDQ-3_3") (pintype "power_in"))
      (node (ref "IC6") (pin "43") (pinfunction "VDDQ-43_43") (pintype "power_in"))
      (node (ref "IC6") (pin "49") (pinfunction "VDDQ-49_49") (pintype "power_in"))
      (node (ref "IC6") (pin "9") (pinfunction "VDDQ-9_9") (pintype "power_in"))
      (node (ref "IC7") (pin "8") (pinfunction "VCC_8") (pintype "power_in"))
      (node (ref "J1") (pin "4") (pinfunction "VDD_4") (pintype "power_in"))
      (node (ref "JP2") (pin "2") (pinfunction "2_2") (pintype "passive"))
      (node (ref "JP5") (pin "1") (pinfunction "1_1") (pintype "passive"))
      (node (ref "JP6") (pin "NO") (pinfunction "NO_NO") (pintype "passive"))
      (node (ref "JP8") (pin "NC") (pinfunction "NC_NC") (pintype "passive"))
      (node (ref "LCD1") (pin "4") (pinfunction "VDD_4") (pintype "power_in"))
      (node (ref "R1") (pin "1") (pinfunction "1_1") (pintype "passive"))
      (node (ref "R14") (pin "1") (pinfunction "1_1") (pintype "passive"))
      (node (ref "R15") (pin "1") (pinfunction "1_1") (pintype "passive"))
      (node (ref "R16") (pin "1") (pinfunction "1_1") (pintype "passive"))
      (node (ref "R21") (pin "1") (pinfunction "1_1") (pintype "passive"))
      (node (ref "R22") (pin "1") (pinfunction "1_1") (pintype "passive"))
      (node (ref "R26") (pin "2") (pinfunction "2_2") (pintype "passive"))
      (node (ref "R30") (pin "2") (pinfunction "2_2") (pintype "passive"))
      (node (ref "R31") (pin "2") (pinfunction "2_2") (pintype "passive"))
      (node (ref "R35") (pin "1") (pinfunction "1_1") (pintype "passive"))
      (node (ref "R38") (pin "1") (pinfunction "1_1") (pintype "passive"))
      (node (ref "R39") (pin "1") (pinfunction "1_1") (pintype "passive"))
      (node (ref "R40") (pin "1") (pinfunction "1_1") (pintype "passive"))
      (node (ref "R42") (pin "1") (pinfunction "1_1") (pintype "passive"))
      (node (ref "R45") (pin "1") (pinfunction "1_1") (pintype "passive"))
      (node (ref "R46") (pin "1") (pinfunction "1_1") (pintype "passive"))
      (node (ref "R48") (pin "1") (pinfunction "1_1") (pintype "passive"))
      (node (ref "R6") (pin "1") (pinfunction "1_1") (pintype "passive"))
      (node (ref "VBUS") (pin "A") (pinfunction "A_A") (pintype "passive"))
      (node (ref "X1") (pin "7") (pinfunction "1_7") (pintype "passive"))
      (node (ref "X2") (pin "16") (pinfunction "1_16") (pintype "passive"))
      (node (ref "X5") (pin "12") (pinfunction "YELLOW_A_12") (pintype "passive"))
      (node (ref "X5") (pin "9") (pinfunction "GREEN-A_9") (pintype "passive"))
    )
    (net (code "2") (name "+3V3(A)") (class "Default")
      (node (ref "C59") (pin "2") (pinfunction "2_2") (pintype "passive"))
      (node (ref "C61") (pin "2") (pinfunction "2_2") (pintype "passive"))
      (node (ref "C66") (pin "1") (pinfunction "1_1") (pintype "passive"))
      (node (ref "FB2") (pin "P$2") (pinfunction "2_P$2") (pintype "passive"))
      (node (ref "IC14") (pin "22") (pinfunction "AVDD33_22") (pintype "power_in"))
      (node (ref "X5") (pin "3") (pinfunction "CT_3") (pintype "input"))
      (node (ref "X5") (pin "6") (pinfunction "CR_6") (pintype "input"))
    )
    (net (code "3") (name "+5V") (class "Default")
      (node (ref "C13") (pin "1") (pinfunction "+_1") (pintype "passive"))
      (node (ref "C14") (pin "1") (pinfunction "1_1") (pintype "passive"))
      (node (ref "C2") (pin "1") (pinfunction "1_1") (pintype "passive"))
      (node (ref "C47") (pin "1") (pinfunction "1_1") (pintype "passive"))
      (node (ref "D1") (pin "C") (pinfunction "C_C") (pintype "passive"))
      (node (ref "IC1") (pin "6") (pinfunction "VCC_6") (pintype "passive"))
      (node (ref "IC4") (pin "3") (pinfunction "IN_3") (pintype "input"))
      (node (ref "IC8") (pin "5") (pinfunction "IN_5") (pintype "input"))
      (node (ref "JP8") (pin "NO") (pinfunction "NO_NO") (pintype "passive"))
      (node (ref "L1") (pin "1") (pinfunction "1_1") (pintype "passive"))
      (node (ref "R23") (pin "1") (pinfunction "1_1") (pintype "passive"))
      (node (ref "X1") (pin "35") (pinfunction "1_35") (pintype "passive"))
      (node (ref "X1") (pin "36") (pinfunction "1_36") (pintype "passive"))
      (node (ref "X2") (pin "5") (pinfunction "1_5") (pintype "passive"))
      (node (ref "X2") (pin "6") (pinfunction "1_6") (pintype "passive"))
    )
    (net (code "4") (name "+12V") (class "Default")
      (node (ref "X1") (pin "37") (pinfunction "1_37") (pintype "passive"))
      (node (ref "X1") (pin "38") (pinfunction "1_38") (pintype "passive"))
      (node (ref "X2") (pin "3") (pinfunction "1_3") (pintype "passive"))
      (node (ref "X2") (pin "4") (pinfunction "1_4") (pintype "passive"))
    )
    (net (code "5") (name "+VAUX") (class "Default")
      (node (ref "JP3") (pin "2") (pinfunction "2_2") (pintype "passive"))
      (node (ref "X1") (pin "5") (pinfunction "1_5") (pintype "passive"))
      (node (ref "X2") (pin "10") (pinfunction "1_10") (pintype "passive"))
    )
    (net (code "12") (name "BOOT0") (class "Default")
      (node (ref "BOOT1") (pin "1") (pinfunction "1_1") (pintype "passive"))
      (node (ref "IC3") (pin "166") (pinfunction "BOOT0_166") (pintype "input"))
      (node (ref "R13") (pin "2") (pinfunction "2_2") (pintype "passive"))
      (node (ref "X2") (pin "2") (pinfunction "1_2") (pintype "passive"))
    )
    (net (code "13") (name "BYPASS_REG") (class "Default")
      (node (ref "IC3") (pin "48") (pinfunction "BYPASS_REG_48") (pintype "input"))
      (node (ref "R12") (pin "2") (pinfunction "2_2") (pintype "passive"))
    )
    (net (code "14") (name "DAC_OUT1") (class "Default")
      (node (ref "IC3") (pin "50") (pinfunction "PA4_50") (pintype "bidirectional"))
      (node (ref "Q2") (pin "1") (pinfunction "G_1") (pintype "passive"))
    )
    (net (code "15") (name "DIN2") (class "Default")
      (node (ref "IC3") (pin "8") (pinfunction "PC13_8") (pintype "bidirectional"))
      (node (ref "R9") (pin "2") (pinfunction "2_2") (pintype "passive"))
    )
    (net (code "16") (name "DOUT2") (class "Default")
      (node (ref "IC2") (pin "7") (pinfunction "I_7") (pintype "input"))
      (node (ref "IC2") (pin "9") (pinfunction "I_9") (pintype "input"))
      (node (ref "IC3") (pin "163") (pinfunction "PB5_163") (pintype "bidirectional"))
    )
    (net (code "17") (name "ENC_A") (class "Default")
      (node (ref "C6") (pin "2") (pinfunction "2_2") (pintype "passive"))
      (node (ref "IC3") (pin "119") (pinfunction "PC6_119") (pintype "bidirectional"))
      (node (ref "R2") (pin "1") (pinfunction "1_1") (pintype "passive"))
    )
    (net (code "18") (name "ENC_B") (class "Default")
      (node (ref "C7") (pin "1") (pinfunction "1_1") (pintype "passive"))
      (node (ref "IC3") (pin "120") (pinfunction "PC7_120") (pintype "bidirectional"))
      (node (ref "R10") (pin "1") (pinfunction "1_1") (pintype "passive"))
    )
    (net (code "19") (name "ENC_SW") (class "Default")
      (node (ref "C3") (pin "2") (pinfunction "2_2") (pintype "passive"))
      (node (ref "IC3") (pin "173") (pinfunction "PI4_173") (pintype "bidirectional"))
      (node (ref "SW2") (pin "E") (pinfunction "2_E") (pintype "passive"))
    )
    (net (code "20") (name "ETH_COL") (class "Default")
      (node (ref "IC3") (pin "47") (pinfunction "PA3_47") (pintype "bidirectional"))
      (node (ref "RN2") (pin "2") (pinfunction "1_2") (pintype "passive"))
    )
    (net (code "21") (name "ETH_CRS") (class "Default")
      (node (ref "IC3") (pin "40") (pinfunction "PA0_40") (pintype "bidirectional"))
      (node (ref "JP9") (pin "1") (pinfunction "1_1") (pintype "passive"))
      (node (ref "RN1") (pin "4") (pinfunction "1_4") (pintype "passive"))
    )
    (net (code "22") (name "ETH_MDC") (class "Default")
      (node (ref "IC14") (pin "31") (pinfunction "MDC_31") (pintype "input"))
      (node (ref "IC3") (pin "33") (pinfunction "PC1_33") (pintype "bidirectional"))
    )
    (net (code "23") (name "ETH_MDIO") (class "Default")
      (node (ref "IC14") (pin "30") (pinfunction "MDIO_30") (pintype "bidirectional"))
      (node (ref "IC3") (pin "42") (pinfunction "PA2_42") (pintype "bidirectional"))
      (node (ref "R31") (pin "1") (pinfunction "1_1") (pintype "passive"))
    )
    (net (code "24") (name "ETH_RXD0") (class "Default")
      (node (ref "IC3") (pin "54") (pinfunction "PC4_54") (pintype "bidirectional"))
      (node (ref "RN2") (pin "3") (pinfunction "1_3") (pintype "passive"))
    )
    (net (code "25") (name "ETH_RXD1") (class "Default")
      (node (ref "IC3") (pin "55") (pinfunction "PC5_55") (pintype "bidirectional"))
      (node (ref "RN2") (pin "4") (pinfunction "1_4") (pintype "passive"))
    )
    (net (code "26") (name "ETH_RXD2") (class "Default")
      (node (ref "IC3") (pin "83") (pinfunction "PH6_83") (pintype "bidirectional"))
      (node (ref "RN3") (pin "1") (pinfunction "1_1") (pintype "passive"))
    )
    (net (code "27") (name "ETH_RXD3") (class "Default")
      (node (ref "IC3") (pin "84") (pinfunction "PH7_84") (pintype "bidirectional"))
      (node (ref "RN3") (pin "2") (pinfunction "1_2") (pintype "passive"))
    )
    (net (code "28") (name "ETH_RX_CLK") (class "Default")
      (node (ref "IC3") (pin "41") (pinfunction "PA1_41") (pintype "bidirectional"))
      (node (ref "RN1") (pin "2") (pinfunction "1_2") (pintype "passive"))
    )
    (net (code "29") (name "ETH_RX_DV") (class "Default")
      (node (ref "IC3") (pin "53") (pinfunction "PA7_53") (pintype "bidirectional"))
      (node (ref "RN1") (pin "3") (pinfunction "1_3") (pintype "passive"))
    )
    (net (code "30") (name "ETH_RX_ERR") (class "Default")
      (node (ref "IC3") (pin "79") (pinfunction "PB10_79") (pintype "bidirectional"))
      (node (ref "JP12") (pin "2") (pinfunction "2_2") (pintype "passive"))
    )
    (net (code "31") (name "ETH_TXD0") (class "Default")
      (node (ref "IC3") (pin "85") (pinfunction "PB12_85") (pintype "bidirectional"))
      (node (ref "RN4") (pin "1") (pinfunction "1_1") (pintype "passive"))
    )
    (net (code "32") (name "ETH_TXD1") (class "Default")
      (node (ref "IC3") (pin "86") (pinfunction "PB13_86") (pintype "bidirectional"))
      (node (ref "RN4") (pin "2") (pinfunction "1_2") (pintype "passive"))
    )
    (net (code "33") (name "ETH_TXD2") (class "Default")
      (node (ref "IC3") (pin "34") (pinfunction "PC2_34") (pintype "bidirectional"))
      (node (ref "RN4") (pin "3") (pinfunction "1_3") (pintype "passive"))
    )
    (net (code "34") (name "ETH_TXD3") (class "Default")
      (node (ref "IC3") (pin "167") (pinfunction "PB8_167") (pintype "bidirectional"))
      (node (ref "RN4") (pin "4") (pinfunction "1_4") (pintype "passive"))
    )
    (net (code "35") (name "ETH_TX_CLK") (class "Default")
      (node (ref "IC3") (pin "35") (pinfunction "PC3_35") (pintype "bidirectional"))
      (node (ref "RN3") (pin "3") (pinfunction "1_3") (pintype "passive"))
    )
    (net (code "36") (name "ETH_TX_EN") (class "Default")
      (node (ref "IC3") (pin "80") (pinfunction "PB11_80") (pintype "bidirectional"))
      (node (ref "RN3") (pin "4") (pinfunction "1_4") (pintype "passive"))
    )
    (net (code "37") (name "FMC_A0") (class "Default")
      (node (ref "IC3") (pin "16") (pinfunction "PF0_16") (pintype "bidirectional"))
      (node (ref "IC6") (pin "23") (pinfunction "A0_23") (pintype "input"))
    )
    (net (code "38") (name "FMC_A1") (class "Default")
      (node (ref "IC3") (pin "17") (pinfunction "PF1_17") (pintype "bidirectional"))
      (node (ref "IC6") (pin "24") (pinfunction "A1_24") (pintype "input"))
    )
    (net (code "39") (name "FMC_A2") (class "Default")
      (node (ref "IC3") (pin "18") (pinfunction "PF2_18") (pintype "bidirectional"))
      (node (ref "IC6") (pin "25") (pinfunction "A2_25") (pintype "input"))
    )
    (net (code "40") (name "FMC_A3") (class "Default")
      (node (ref "IC3") (pin "19") (pinfunction "PF3_19") (pintype "bidirectional"))
      (node (ref "IC6") (pin "26") (pinfunction "A3_26") (pintype "input"))
    )
    (net (code "41") (name "FMC_A4") (class "Default")
      (node (ref "IC3") (pin "20") (pinfunction "PF4_20") (pintype "bidirectional"))
      (node (ref "IC6") (pin "29") (pinfunction "A4_29") (pintype "input"))
    )
    (net (code "42") (name "FMC_A5") (class "Default")
      (node (ref "IC3") (pin "21") (pinfunction "PF5_21") (pintype "bidirectional"))
      (node (ref "IC6") (pin "30") (pinfunction "A5_30") (pintype "input"))
    )
    (net (code "43") (name "FMC_A6") (class "Default")
      (node (ref "IC3") (pin "60") (pinfunction "PF12_60") (pintype "bidirectional"))
      (node (ref "IC6") (pin "31") (pinfunction "A6_31") (pintype "input"))
    )
    (net (code "44") (name "FMC_A7") (class "Default")
      (node (ref "IC3") (pin "63") (pinfunction "PF13_63") (pintype "bidirectional"))
      (node (ref "IC6") (pin "32") (pinfunction "A7_32") (pintype "input"))
    )
    (net (code "45") (name "FMC_A8") (class "Default")
      (node (ref "IC3") (pin "64") (pinfunction "PF14_64") (pintype "bidirectional"))
      (node (ref "IC6") (pin "33") (pinfunction "A8_33") (pintype "input"))
    )
    (net (code "46") (name "FMC_A9") (class "Default")
      (node (ref "IC3") (pin "65") (pinfunction "PF15_65") (pintype "bidirectional"))
      (node (ref "IC6") (pin "34") (pinfunction "A9_34") (pintype "input"))
    )
    (net (code "47") (name "FMC_A10") (class "Default")
      (node (ref "IC3") (pin "66") (pinfunction "PG0_66") (pintype "bidirectional"))
      (node (ref "IC6") (pin "22") (pinfunction "A10/AP_22") (pintype "input"))
    )
    (net (code "48") (name "FMC_A11") (class "Default")
      (node (ref "IC3") (pin "67") (pinfunction "PG1_67") (pintype "bidirectional"))
      (node (ref "IC6") (pin "35") (pinfunction "A11_35") (pintype "input"))
    )
    (net (code "49") (name "FMC_BA0") (class "Default")
      (node (ref "IC3") (pin "112") (pinfunction "PG4_112") (pintype "bidirectional"))
      (node (ref "IC6") (pin "20") (pinfunction "BA0_20") (pintype "input"))
    )
    (net (code "50") (name "FMC_BA1") (class "Default")
      (node (ref "IC3") (pin "113") (pinfunction "PG5_113") (pintype "bidirectional"))
      (node (ref "IC6") (pin "21") (pinfunction "BA1_21") (pintype "input"))
    )
    (net (code "51") (name "FMC_D0") (class "Default")
      (node (ref "IC3") (pin "97") (pinfunction "PD14_97") (pintype "bidirectional"))
      (node (ref "IC6") (pin "2") (pinfunction "DQ0_2") (pintype "bidirectional"))
    )
    (net (code "52") (name "FMC_D1") (class "Default")
      (node (ref "IC3") (pin "98") (pinfunction "PD15_98") (pintype "bidirectional"))
      (node (ref "IC6") (pin "4") (pinfunction "DQ1_4") (pintype "bidirectional"))
    )
    (net (code "53") (name "FMC_D2") (class "Default")
      (node (ref "IC3") (pin "142") (pinfunction "PD0_142") (pintype "bidirectional"))
      (node (ref "IC6") (pin "5") (pinfunction "DQ2_5") (pintype "bidirectional"))
    )
    (net (code "54") (name "FMC_D3") (class "Default")
      (node (ref "IC3") (pin "143") (pinfunction "PD1_143") (pintype "bidirectional"))
      (node (ref "IC6") (pin "7") (pinfunction "DQ3_7") (pintype "bidirectional"))
    )
    (net (code "55") (name "FMC_D4") (class "Default")
      (node (ref "IC3") (pin "68") (pinfunction "PE7_68") (pintype "bidirectional"))
      (node (ref "IC6") (pin "8") (pinfunction "DQ4_8") (pintype "bidirectional"))
    )
    (net (code "56") (name "FMC_D5") (class "Default")
      (node (ref "IC3") (pin "69") (pinfunction "PE8_69") (pintype "bidirectional"))
      (node (ref "IC6") (pin "10") (pinfunction "DQ5_10") (pintype "bidirectional"))
    )
    (net (code "57") (name "FMC_D6") (class "Default")
      (node (ref "IC3") (pin "70") (pinfunction "PE9_70") (pintype "bidirectional"))
      (node (ref "IC6") (pin "11") (pinfunction "DQ6_11") (pintype "bidirectional"))
    )
    (net (code "58") (name "FMC_D7") (class "Default")
      (node (ref "IC3") (pin "73") (pinfunction "PE10_73") (pintype "bidirectional"))
      (node (ref "IC6") (pin "13") (pinfunction "DQ7_13") (pintype "bidirectional"))
    )
    (net (code "59") (name "FMC_D8") (class "Default")
      (node (ref "IC3") (pin "74") (pinfunction "PE11_74") (pintype "bidirectional"))
      (node (ref "IC6") (pin "42") (pinfunction "DQ8_42") (pintype "bidirectional"))
    )
    (net (code "60") (name "FMC_D9") (class "Default")
      (node (ref "IC3") (pin "75") (pinfunction "PE12_75") (pintype "bidirectional"))
      (node (ref "IC6") (pin "44") (pinfunction "DQ9_44") (pintype "bidirectional"))
    )
    (net (code "61") (name "FMC_D10") (class "Default")
      (node (ref "IC3") (pin "76") (pinfunction "PE13_76") (pintype "bidirectional"))
      (node (ref "IC6") (pin "45") (pinfunction "DQ10_45") (pintype "bidirectional"))
    )
    (net (code "62") (name "FMC_D11") (class "Default")
      (node (ref "IC3") (pin "77") (pinfunction "PE14_77") (pintype "bidirectional"))
      (node (ref "IC6") (pin "47") (pinfunction "DQ11_47") (pintype "bidirectional"))
    )
    (net (code "63") (name "FMC_D12") (class "Default")
      (node (ref "IC3") (pin "78") (pinfunction "PE15_78") (pintype "bidirectional"))
      (node (ref "IC6") (pin "48") (pinfunction "DQ12_48") (pintype "bidirectional"))
    )
    (net (code "64") (name "FMC_D13") (class "Default")
      (node (ref "IC3") (pin "89") (pinfunction "PD8_89") (pintype "bidirectional"))
      (node (ref "IC6") (pin "50") (pinfunction "DQ13_50") (pintype "bidirectional"))
    )
    (net (code "65") (name "FMC_D14") (class "Default")
      (node (ref "IC3") (pin "90") (pinfunction "PD9_90") (pintype "bidirectional"))
      (node (ref "IC6") (pin "51") (pinfunction "DQ14_51") (pintype "bidirectional"))
    )
    (net (code "66") (name "FMC_D15") (class "Default")
      (node (ref "IC3") (pin "91") (pinfunction "PD10_91") (pintype "bidirectional"))
      (node (ref "IC6") (pin "53") (pinfunction "DQ15_53") (pintype "bidirectional"))
    )
    (net (code "67") (name "FMC_NBL0") (class "Default")
      (node (ref "IC3") (pin "169") (pinfunction "PE0_169") (pintype "bidirectional"))
      (node (ref "IC6") (pin "15") (pinfunction "LDQM_15") (pintype "input"))
    )
    (net (code "68") (name "FMC_NBL1") (class "Default")
      (node (ref "IC3") (pin "170") (pinfunction "PE1_170") (pintype "bidirectional"))
      (node (ref "IC6") (pin "39") (pinfunction "UDQM_39") (pintype "input"))
    )
    (net (code "69") (name "FMC_SDCKE0") (class "Default")
      (node (ref "IC3") (pin "43") (pinfunction "PH2_43") (pintype "bidirectional"))
      (node (ref "IC6") (pin "37") (pinfunction "CKE_37") (pintype "input"))
    )
    (net (code "70") (name "FMC_SDCLK") (class "Default")
      (node (ref "IC3") (pin "116") (pinfunction "PG8_116") (pintype "bidirectional"))
      (node (ref "IC6") (pin "38") (pinfunction "CLK_38") (pintype "input"))
    )
    (net (code "71") (name "FMC_SDNCAS") (class "Default")
      (node (ref "IC3") (pin "160") (pinfunction "PG15_160") (pintype "bidirectional"))
      (node (ref "IC6") (pin "17") (pinfunction "~{CAS}_17") (pintype "input"))
    )
    (net (code "72") (name "FMC_SDNE0") (class "Default")
      (node (ref "IC3") (pin "44") (pinfunction "PH3_44") (pintype "bidirectional"))
      (node (ref "IC6") (pin "19") (pinfunction "~{CS}_19") (pintype "input"))
    )
    (net (code "73") (name "FMC_SDNRAS") (class "Default")
      (node (ref "IC3") (pin "59") (pinfunction "PF11_59") (pintype "bidirectional"))
      (node (ref "IC6") (pin "18") (pinfunction "~{RAS}_18") (pintype "input"))
    )
    (net (code "74") (name "FMC_SDNWE") (class "Default")
      (node (ref "IC3") (pin "46") (pinfunction "PH5_46") (pintype "bidirectional"))
      (node (ref "IC6") (pin "16") (pinfunction "~{WE}_16") (pintype "input"))
    )
    (net (code "75") (name "GND") (class "Default")
      (node (ref "B1") (pin "2") (pinfunction "-_2") (pintype "passive"))
      (node (ref "C1") (pin "2") (pinfunction "2_2") (pintype "passive"))
      (node (ref "C10") (pin "2") (pinfunction "2_2") (pintype "passive"))
      (node (ref "C11") (pin "1") (pinfunction "1_1") (pintype "passive"))
      (node (ref "C12") (pin "2") (pinfunction "2_2") (pintype "passive"))
      (node (ref "C13") (pin "2") (pinfunction "-_2") (pintype "passive"))
      (node (ref "C14") (pin "2") (pinfunction "2_2") (pintype "passive"))
      (node (ref "C15") (pin "-") (pinfunction "-_-") (pintype "passive"))
      (node (ref "C16") (pin "2") (pinfunction "2_2") (pintype "passive"))
      (node (ref "C17") (pin "2") (pinfunction "2_2") (pintype "passive"))
      (node (ref "C18") (pin "2") (pinfunction "2_2") (pintype "passive"))
      (node (ref "C19") (pin "2") (pinfunction "2_2") (pintype "passive"))
      (node (ref "C2") (pin "2") (pinfunction "2_2") (pintype "passive"))
      (node (ref "C20") (pin "2") (pinfunction "2_2") (pintype "passive"))
      (node (ref "C21") (pin "2") (pinfunction "2_2") (pintype "passive"))
      (node (ref "C22") (pin "-") (pinfunction "-_-") (pintype "passive"))
      (node (ref "C23") (pin "2") (pinfunction "2_2") (pintype "passive"))
      (node (ref "C24") (pin "2") (pinfunction "2_2") (pintype "passive"))
      (node (ref "C25") (pin "2") (pinfunction "2_2") (pintype "passive"))
      (node (ref "C26") (pin "2") (pinfunction "2_2") (pintype "passive"))
      (node (ref "C27") (pin "2") (pinfunction "2_2") (pintype "passive"))
      (node (ref "C28") (pin "2") (pinfunction "2_2") (pintype "passive"))
      (node (ref "C29") (pin "2") (pinfunction "2_2") (pintype "passive"))
      (node (ref "C3") (pin "1") (pinfunction "1_1") (pintype "passive"))
      (node (ref "C30") (pin "2") (pinfunction "2_2") (pintype "passive"))
      (node (ref "C31") (pin "2") (pinfunction "2_2") (pintype "passive"))
      (node (ref "C32") (pin "2") (pinfunction "2_2") (pintype "passive"))
      (node (ref "C33") (pin "2") (pinfunction "2_2") (pintype "passive"))
      (node (ref "C34") (pin "2") (pinfunction "2_2") (pintype "passive"))
      (node (ref "C35") (pin "2") (pinfunction "2_2") (pintype "passive"))
      (node (ref "C36") (pin "2") (pinfunction "2_2") (pintype "passive"))
      (node (ref "C37") (pin "2") (pinfunction "2_2") (pintype "passive"))
      (node (ref "C38") (pin "2") (pinfunction "2_2") (pintype "passive"))
      (node (ref "C39") (pin "2") (pinfunction "2_2") (pintype "passive"))
      (node (ref "C4") (pin "1") (pinfunction "1_1") (pintype "passive"))
      (node (ref "C40") (pin "1") (pinfunction "1_1") (pintype "passive"))
      (node (ref "C41") (pin "2") (pinfunction "2_2") (pintype "passive"))
      (node (ref "C42") (pin "2") (pinfunction "2_2") (pintype "passive"))
      (node (ref "C43") (pin "2") (pinfunction "2_2") (pintype "passive"))
      (node (ref "C44") (pin "2") (pinfunction "2_2") (pintype "passive"))
      (node (ref "C45") (pin "2") (pinfunction "2_2") (pintype "passive"))
      (node (ref "C46") (pin "2") (pinfunction "2_2") (pintype "passive"))
      (node (ref "C47") (pin "2") (pinfunction "2_2") (pintype "passive"))
      (node (ref "C48") (pin "2") (pinfunction "2_2") (pintype "passive"))
      (node (ref "C49") (pin "-") (pinfunction "-_-") (pintype "passive"))
      (node (ref "C5") (pin "2") (pinfunction "2_2") (pintype "passive"))
      (node (ref "C50") (pin "2") (pinfunction "2_2") (pintype "passive"))
      (node (ref "C51") (pin "2") (pinfunction "2_2") (pintype "passive"))
      (node (ref "C52") (pin "1") (pinfunction "1_1") (pintype "passive"))
      (node (ref "C53") (pin "1") (pinfunction "1_1") (pintype "passive"))
      (node (ref "C54") (pin "1") (pinfunction "1_1") (pintype "passive"))
      (node (ref "C55") (pin "1") (pinfunction "1_1") (pintype "passive"))
      (node (ref "C56") (pin "1") (pinfunction "1_1") (pintype "passive"))
      (node (ref "C57") (pin "2") (pinfunction "2_2") (pintype "passive"))
      (node (ref "C58") (pin "2") (pinfunction "2_2") (pintype "passive"))
      (node (ref "C59") (pin "1") (pinfunction "1_1") (pintype "passive"))
      (node (ref "C6") (pin "1") (pinfunction "1_1") (pintype "passive"))
      (node (ref "C60") (pin "2") (pinfunction "2_2") (pintype "passive"))
      (node (ref "C61") (pin "1") (pinfunction "1_1") (pintype "passive"))
      (node (ref "C62") (pin "2") (pinfunction "2_2") (pintype "passive"))
      (node (ref "C63") (pin "2") (pinfunction "2_2") (pintype "passive"))
      (node (ref "C64") (pin "-") (pinfunction "-_-") (pintype "passive"))
      (node (ref "C65") (pin "2") (pinfunction "2_2") (pintype "passive"))
      (node (ref "C66") (pin "2") (pinfunction "2_2") (pintype "passive"))
      (node (ref "C67") (pin "2") (pinfunction "2_2") (pintype "passive"))
      (node (ref "C68") (pin "2") (pinfunction "2_2") (pintype "passive"))
      (node (ref "C7") (pin "2") (pinfunction "2_2") (pintype "passive"))
      (node (ref "C9") (pin "1") (pinfunction "1_1") (pintype "passive"))
      (node (ref "D1") (pin "A") (pinfunction "A_A") (pintype "passive"))
      (node (ref "IC1") (pin "3") (pinfunction "GND_3") (pintype "power_in"))
      (node (ref "IC10") (pin "3") (pinfunction "GND_3") (pintype "power_in"))
      (node (ref "IC11") (pin "3") (pinfunction "GND_3") (pintype "power_in"))
      (node (ref "IC12") (pin "13") (pinfunction "A1_13") (pintype "input"))
      (node (ref "IC12") (pin "14") (pinfunction "A0_14") (pintype "input"))
      (node (ref "IC12") (pin "6") (pinfunction "GND_6") (pintype "passive"))
      (node (ref "IC13") (pin "3") (pinfunction "GND_3") (pintype "power_in"))
      (node (ref "IC14") (pin "15") (pinfunction "AGND-15_15") (pintype "power_in"))
      (node (ref "IC14") (pin "19") (pinfunction "AGND-19_19") (pintype "power_in"))
      (node (ref "IC14") (pin "35") (pinfunction "IOGND-35_35") (pintype "power_in"))
      (node (ref "IC14") (pin "36") (pinfunction "DGND_36") (pintype "power_in"))
      (node (ref "IC14") (pin "47") (pinfunction "IOGND-47_47") (pintype "power_in"))
      (node (ref "IC2") (pin "8") (pinfunction "VSS_8") (pintype "power_in"))
      (node (ref "IC3") (pin "103") (pinfunction "VSSDSI_2_103") (pintype "power_in"))
      (node (ref "IC3") (pin "109") (pinfunction "VSSDSI_109") (pintype "power_in"))
      (node (ref "IC3") (pin "117") (pinfunction "VSS_7_117") (pintype "power_in"))
      (node (ref "IC3") (pin "130") (pinfunction "VSS_8_130") (pintype "power_in"))
      (node (ref "IC3") (pin "135") (pinfunction "VSS_9_135") (pintype "power_in"))
      (node (ref "IC3") (pin "14") (pinfunction "VSS_2_14") (pintype "power_in"))
      (node (ref "IC3") (pin "148") (pinfunction "VSS_10_148") (pintype "power_in"))
      (node (ref "IC3") (pin "158") (pinfunction "VSS_158") (pintype "power_in"))
      (node (ref "IC3") (pin "22") (pinfunction "VSS_3_22") (pintype "power_in"))
      (node (ref "IC3") (pin "37") (pinfunction "VSSA_37") (pintype "power_in"))
      (node (ref "IC3") (pin "61") (pinfunction "VSS_4_61") (pintype "power_in"))
      (node (ref "IC3") (pin "71") (pinfunction "VSS_5_71") (pintype "power_in"))
      (node (ref "IC3") (pin "95") (pinfunction "VSS_6_95") (pintype "power_in"))
      (node (ref "IC4") (pin "1") (pinfunction "ADJ_1") (pintype "input"))
      (node (ref "IC5") (pin "3") (pinfunction "GND_3") (pintype "power_in"))
      (node (ref "IC6") (pin "12") (pinfunction "GNDQ-12_12") (pintype "power_in"))
      (node (ref "IC6") (pin "28") (pinfunction "GND-28_28") (pintype "power_in"))
      (node (ref "IC6") (pin "41") (pinfunction "GND_41") (pintype "power_in"))
      (node (ref "IC6") (pin "46") (pinfunction "GNDQ-46_46") (pintype "power_in"))
      (node (ref "IC6") (pin "52") (pinfunction "GNDQ-52_52") (pintype "power_in"))
      (node (ref "IC6") (pin "54") (pinfunction "GND-54_54") (pintype "power_in"))
      (node (ref "IC6") (pin "6") (pinfunction "GNDQ-6_6") (pintype "power_in"))
      (node (ref "IC7") (pin "1") (pinfunction "A0_1") (pintype "input"))
      (node (ref "IC7") (pin "2") (pinfunction "A1_2") (pintype "input"))
      (node (ref "IC7") (pin "3") (pinfunction "A2_3") (pintype "input"))
      (node (ref "IC7") (pin "4") (pinfunction "GND_4") (pintype "passive"))
      (node (ref "IC7") (pin "7") (pinfunction "WP_7") (pintype "input"))
      (node (ref "IC8") (pin "2") (pinfunction "GND_2") (pintype "power_in"))
      (node (ref "IC9") (pin "2") (pinfunction "GND_2") (pintype "power_in"))
      (node (ref "J1") (pin "6") (pinfunction "VSS_6") (pintype "power_in"))
      (node (ref "J1") (pin "S") (pinfunction "SH_S") (pintype "passive"))
      (node (ref "J1") (pin "S1") (pinfunction "SH_S1") (pintype "passive"))
      (node (ref "J1") (pin "S2") (pinfunction "SH_S2") (pintype "passive"))
      (node (ref "J1") (pin "SW2") (pinfunction "SW2_SW2") (pintype "passive"))
      (node (ref "J2") (pin "5") (pinfunction "GND_5") (pintype "passive"))
      (node (ref "JP1") (pin "1") (pinfunction "1_1") (pintype "passive"))
      (node (ref "JP6") (pin "NC") (pinfunction "NC_NC") (pintype "passive"))
      (node (ref "JP7") (pin "NC") (pinfunction "NC_NC") (pintype "passive"))
      (node (ref "LCD1") (pin "29") (pinfunction "GND-29_29") (pintype "power_in"))
      (node (ref "LCD1") (pin "3") (pinfunction "GND-3_3") (pintype "power_in"))
      (node (ref "Q1") (pin "E") (pinfunction "E_E") (pintype "passive"))
      (node (ref "Q2") (pin "2") (pinfunction "S_2") (pintype "passive"))
      (node (ref "R12") (pin "1") (pinfunction "1_1") (pintype "passive"))
      (node (ref "R13") (pin "1") (pinfunction "1_1") (pintype "passive"))
      (node (ref "R18") (pin "1") (pinfunction "1_1") (pintype "passive"))
      (node (ref "R25") (pin "2") (pinfunction "2_2") (pintype "passive"))
      (node (ref "R34") (pin "1") (pinfunction "1_1") (pintype "passive"))
      (node (ref "R37") (pin "1") (pinfunction "1_1") (pintype "passive"))
      (node (ref "R47") (pin "1") (pinfunction "1_1") (pintype "passive"))
      (node (ref "SW1") (pin "2") (pinfunction "2_2") (pintype "passive"))
      (node (ref "SW2") (pin "C") (pinfunction "C_C") (pintype "passive"))
      (node (ref "SW2") (pin "D") (pinfunction "1_D") (pintype "passive"))
      (node (ref "SW2") (pin "GND1") (pinfunction "C_GND1") (pintype "passive"))
      (node (ref "SW2") (pin "GND2") (pinfunction "C_GND2") (pintype "passive"))
      (node (ref "TP1") (pin "1") (pinfunction "P$1_1") (pintype "bidirectional"))
      (node (ref "X1") (pin "1") (pinfunction "1_1") (pintype "passive"))
      (node (ref "X1") (pin "15") (pinfunction "1_15") (pintype "passive"))
      (node (ref "X1") (pin "16") (pinfunction "1_16") (pintype "passive"))
      (node (ref "X1") (pin "2") (pinfunction "1_2") (pintype "passive"))
      (node (ref "X1") (pin "29") (pinfunction "1_29") (pintype "passive"))
      (node (ref "X1") (pin "30") (pinfunction "1_30") (pintype "passive"))
      (node (ref "X1") (pin "34") (pinfunction "1_34") (pintype "passive"))
      (node (ref "X1") (pin "39") (pinfunction "1_39") (pintype "passive"))
      (node (ref "X1") (pin "40") (pinfunction "1_40") (pintype "passive"))
      (node (ref "X2") (pin "7") (pinfunction "1_7") (pintype "passive"))
      (node (ref "X2") (pin "8") (pinfunction "1_8") (pintype "passive"))
      (node (ref "X2") (pin "9") (pinfunction "1_9") (pintype "passive"))
      (node (ref "X3") (pin "3") (pinfunction "1_3") (pintype "passive"))
      (node (ref "X4") (pin "3") (pinfunction "S_3") (pintype "passive"))
      (node (ref "X5") (pin "4") (pinfunction "GND_4") (pintype "passive"))
      (node (ref "X5") (pin "5") (pinfunction "GND_5") (pintype "passive"))
    )
    (net (code "76") (name "I2C1_SCL") (class "Default")
      (node (ref "IC12") (pin "12") (pinfunction "SCL_12") (pintype "bidirectional"))
      (node (ref "IC3") (pin "164") (pinfunction "PB6_164") (pintype "bidirectional"))
      (node (ref "IC7") (pin "6") (pinfunction "SCL_6") (pintype "bidirectional"))
      (node (ref "R15") (pin "2") (pinfunction "2_2") (pintype "passive"))
      (node (ref "SCL") (pin "1") (pinfunction "1_1") (pintype "passive"))
      (node (ref "X1") (pin "12") (pinfunction "1_12") (pintype "passive"))
    )
    (net (code "77") (name "I2C1_SDA") (class "Default")
      (node (ref "IC12") (pin "11") (pinfunction "SDA_11") (pintype "bidirectional"))
      (node (ref "IC3") (pin "165") (pinfunction "PB7_165") (pintype "bidirectional"))
      (node (ref "IC7") (pin "5") (pinfunction "SDA_5") (pintype "bidirectional"))
      (node (ref "R16") (pin "2") (pinfunction "2_2") (pintype "passive"))
      (node (ref "SDA") (pin "2") (pinfunction "2_2") (pintype "passive"))
      (node (ref "X1") (pin "14") (pinfunction "1_14") (pintype "passive"))
    )
    (net (code "78") (name "IRQ_TOUCH") (class "Default")
      (node (ref "IC12") (pin "10") (pinfunction "~{PENIRQ}_10") (pintype "output"))
      (node (ref "IC3") (pin "151") (pinfunction "PD7_151") (pintype "bidirectional"))
    )
    (net (code "79") (name "LCD_DISP") (class "Default")
      (node (ref "LCD1") (pin "31") (pinfunction "DISP_31") (pintype "input"))
      (node (ref "R30") (pin "1") (pinfunction "1_1") (pintype "passive"))
    )
    (net (code "80") (name "LED_ACT") (class "Default")
      (node (ref "IC14") (pin "26") (pinfunction "AN_EN(LED_ACT/COL)_26") (pintype "output"))
      (node (ref "R35") (pin "2") (pinfunction "2_2") (pintype "passive"))
      (node (ref "R43") (pin "2") (pinfunction "2_2") (pintype "passive"))
    )
    (net (code "81") (name "LED_LINK") (class "Default")
      (node (ref "IC14") (pin "28") (pinfunction "AN_0(LED_LINK)_28") (pintype "output"))
      (node (ref "R42") (pin "2") (pinfunction "2_2") (pintype "passive"))
      (node (ref "R44") (pin "2") (pinfunction "2_2") (pintype "passive"))
    )
    (net (code "82") (name "LED_SPEED") (class "Default")
      (node (ref "IC14") (pin "27") (pinfunction "AN_1(LED_SPEED)_27") (pintype "output"))
      (node (ref "R40") (pin "2") (pinfunction "2_2") (pintype "passive"))
      (node (ref "SPEED") (pin "C") (pinfunction "C_C") (pintype "passive"))
    )
    (net (code "83") (name "LTDC_B3") (class "Default")
      (node (ref "IC3") (pin "154") (pinfunction "PG11_154") (pintype "bidirectional"))
      (node (ref "LCD1") (pin "24") (pinfunction "B3_24") (pintype "input"))
    )
    (net (code "84") (name "LTDC_B4") (class "Default")
      (node (ref "IC3") (pin "155") (pinfunction "PG12_155") (pintype "bidirectional"))
      (node (ref "LCD1") (pin "25") (pinfunction "B4_25") (pintype "input"))
    )
    (net (code "85") (name "LTDC_B5") (class "Default")
      (node (ref "IC3") (pin "174") (pinfunction "PI5_174") (pintype "bidirectional"))
      (node (ref "LCD1") (pin "26") (pinfunction "B5_26") (pintype "input"))
    )
    (net (code "86") (name "LTDC_B6") (class "Default")
      (node (ref "IC3") (pin "175") (pinfunction "PI6_175") (pintype "bidirectional"))
      (node (ref "LCD1") (pin "27") (pinfunction "B6_27") (pintype "input"))
    )
    (net (code "87") (name "LTDC_B7") (class "Default")
      (node (ref "IC3") (pin "176") (pinfunction "PI7_176") (pintype "bidirectional"))
      (node (ref "LCD1") (pin "28") (pinfunction "B7_28") (pintype "input"))
    )
    (net (code "88") (name "LTDC_CLK") (class "Default")
      (node (ref "IC3") (pin "115") (pinfunction "PG7_115") (pintype "bidirectional"))
      (node (ref "LCD1") (pin "30") (pinfunction "CLK_30") (pintype "input"))
    )
    (net (code "89") (name "LTDC_DE") (class "Default")
      (node (ref "IC3") (pin "28") (pinfunction "PF10_28") (pintype "bidirectional"))
      (node (ref "LCD1") (pin "34") (pinfunction "DE/NC2_34") (pintype "passive"))
    )
    (net (code "90") (name "LTDC_G2") (class "Default")
      (node (ref "IC3") (pin "52") (pinfunction "PA6_52") (pintype "bidirectional"))
      (node (ref "LCD1") (pin "15") (pinfunction "G2_15") (pintype "input"))
    )
    (net (code "91") (name "LTDC_G3") (class "Default")
      (node (ref "IC3") (pin "153") (pinfunction "PG10_153") (pintype "bidirectional"))
      (node (ref "LCD1") (pin "16") (pinfunction "G3_16") (pintype "input"))
    )
    (net (code "92") (name "LTDC_G4") (class "Default")
      (node (ref "IC3") (pin "45") (pinfunction "PH4_45") (pintype "bidirectional"))
      (node (ref "LCD1") (pin "17") (pinfunction "G4_17") (pintype "input"))
    )
    (net (code "93") (name "LTDC_G5") (class "Default")
      (node (ref "IC3") (pin "132") (pinfunction "PI0_132") (pintype "bidirectional"))
      (node (ref "LCD1") (pin "18") (pinfunction "G5_18") (pintype "input"))
    )
    (net (code "94") (name "LTDC_G6") (class "Default")
      (node (ref "IC3") (pin "13") (pinfunction "PI11_13") (pintype "bidirectional"))
      (node (ref "LCD1") (pin "19") (pinfunction "G6_19") (pintype "input"))
    )
    (net (code "95") (name "LTDC_G7") (class "Default")
      (node (ref "IC3") (pin "145") (pinfunction "PD3_145") (pintype "bidirectional"))
      (node (ref "LCD1") (pin "20") (pinfunction "G7_20") (pintype "input"))
    )
    (net (code "96") (name "LTDC_HSYNC") (class "Default")
      (node (ref "IC3") (pin "12") (pinfunction "PI10_12") (pintype "bidirectional"))
      (node (ref "LCD1") (pin "32") (pinfunction "HSYNC_32") (pintype "input"))
    )
    (net (code "97") (name "LTDC_R3") (class "Default")
      (node (ref "IC3") (pin "56") (pinfunction "PB0_56") (pintype "bidirectional"))
      (node (ref "LCD1") (pin "8") (pinfunction "R3_8") (pintype "input"))
    )
    (net (code "98") (name "LTDC_R4") (class "Default")
      (node (ref "IC3") (pin "51") (pinfunction "PA5_51") (pintype "bidirectional"))
      (node (ref "LCD1") (pin "9") (pinfunction "R4_9") (pintype "input"))
    )
    (net (code "99") (name "LTDC_R5") (class "Default")
      (node (ref "IC3") (pin "32") (pinfunction "PC0_32") (pintype "bidirectional"))
      (node (ref "LCD1") (pin "10") (pinfunction "R5_10") (pintype "input"))
    )
    (net (code "100") (name "LTDC_R6") (class "Default")
      (node (ref "IC3") (pin "57") (pinfunction "PB1_57") (pintype "bidirectional"))
      (node (ref "LCD1") (pin "11") (pinfunction "R6_11") (pintype "input"))
    )
    (net (code "101") (name "LTDC_R7") (class "Default")
      (node (ref "IC3") (pin "114") (pinfunction "PG6_114") (pintype "bidirectional"))
      (node (ref "LCD1") (pin "12") (pinfunction "R7_12") (pintype "input"))
    )
    (net (code "102") (name "LTDC_VSYNC") (class "Default")
      (node (ref "IC3") (pin "11") (pinfunction "PI9_11") (pintype "bidirectional"))
      (node (ref "LCD1") (pin "33") (pinfunction "VSYNC_33") (pintype "input"))
    )
    (net (code "103") (name "MCLK_25") (class "Default")
      (node (ref "IC3") (pin "122") (pinfunction "PC9_122") (pintype "bidirectional"))
      (node (ref "RN1") (pin "1") (pinfunction "1_1") (pintype "passive"))
    )
    (net (code "104") (name "Net-(B1-+-Pad1)") (class "Default")
      (node (ref "B1") (pin "1") (pinfunction "+_1") (pintype "passive"))
      (node (ref "B1") (pin "3") (pinfunction "+_3") (pintype "passive"))
      (node (ref "JP3") (pin "1") (pinfunction "1_1") (pintype "passive"))
      (node (ref "JP4") (pin "NC") (pinfunction "NC_NC") (pintype "passive"))
    )
    (net (code "105") (name "Net-(C53-Pad2)") (class "Default")
      (node (ref "C53") (pin "2") (pinfunction "2_2") (pintype "passive"))
      (node (ref "JP8") (pin "COM") (pinfunction "COM_COM") (pintype "passive"))
      (node (ref "SP1") (pin "+B") (pinfunction "+_+B") (pintype "passive"))
      (node (ref "SP1") (pin "+B.1") (pinfunction "+_+B.1") (pintype "passive"))
    )
    (net (code "106") (name "Net-(C58-Pad1)") (class "Default")
      (node (ref "C58") (pin "1") (pinfunction "1_1") (pintype "passive"))
      (node (ref "R32") (pin "1") (pinfunction "1_1") (pintype "passive"))
      (node (ref "R33") (pin "2") (pinfunction "2_2") (pintype "passive"))
    )
    (net (code "107") (name "Net-(C60-Pad1)") (class "Default")
      (node (ref "C60") (pin "1") (pinfunction "1_1") (pintype "passive"))
      (node (ref "R36") (pin "1") (pinfunction "1_1") (pintype "passive"))
      (node (ref "R41") (pin "2") (pinfunction "2_2") (pintype "passive"))
    )
    (net (code "108") (name "Net-(IC1-IO1)") (class "Default")
      (node (ref "IC1") (pin "1") (pinfunction "IO1_1") (pintype "bidirectional"))
      (node (ref "R3") (pin "1") (pinfunction "1_1") (pintype "passive"))
      (node (ref "X3") (pin "1") (pinfunction "1_1") (pintype "passive"))
    )
    (net (code "109") (name "Net-(IC1-IO2)") (class "Default")
      (node (ref "IC1") (pin "2") (pinfunction "IO2_2") (pintype "bidirectional"))
      (node (ref "R7") (pin "1") (pinfunction "1_1") (pintype "passive"))
      (node (ref "X3") (pin "2") (pinfunction "1_2") (pintype "passive"))
    )
    (net (code "110") (name "Net-(IC1-IO3)") (class "Default")
      (node (ref "IC1") (pin "4") (pinfunction "IO3_4") (pintype "bidirectional"))
      (node (ref "IC2") (pin "12") (pinfunction "O_12") (pintype "output"))
      (node (ref "IC2") (pin "4") (pinfunction "O_4") (pintype "output"))
      (node (ref "X3") (pin "4") (pinfunction "1_4") (pintype "passive"))
    )
    (net (code "111") (name "Net-(IC1-IO4)") (class "Default")
      (node (ref "IC1") (pin "5") (pinfunction "IO4_5") (pintype "bidirectional"))
      (node (ref "IC2") (pin "10") (pinfunction "O_10") (pintype "output"))
      (node (ref "IC2") (pin "6") (pinfunction "O_6") (pintype "output"))
      (node (ref "X3") (pin "5") (pinfunction "1_5") (pintype "passive"))
    )
    (net (code "112") (name "Net-(IC2A-I)") (class "Default")
      (node (ref "IC2") (pin "3") (pinfunction "I_3") (pintype "input"))
      (node (ref "R8") (pin "2") (pinfunction "2_2") (pintype "passive"))
    )
    (net (code "113") (name "Net-(IC2A-O)") (class "Default")
      (node (ref "IC2") (pin "2") (pinfunction "O_2") (pintype "output"))
      (node (ref "R9") (pin "1") (pinfunction "1_1") (pintype "passive"))
    )
    (net (code "114") (name "Net-(IC2F-I)") (class "Default")
      (node (ref "IC2") (pin "14") (pinfunction "I_14") (pintype "input"))
      (node (ref "R4") (pin "2") (pinfunction "2_2") (pintype "passive"))
    )
    (net (code "115") (name "Net-(IC2F-O)") (class "Default")
      (node (ref "IC2") (pin "15") (pinfunction "O_15") (pintype "output"))
      (node (ref "R5") (pin "1") (pinfunction "1_1") (pintype "passive"))
    )
    (net (code "116") (name "Net-(IC3D-VCAPDSI)") (class "Default")
      (node (ref "IC3") (pin "100") (pinfunction "VCAPDSI_100") (pintype "power_in"))
      (node (ref "IC3") (pin "106") (pinfunction "VDD12DSI_106") (pintype "power_in"))
    )
    (net (code "117") (name "Net-(IC9-SW)") (class "Default")
      (node (ref "D2") (pin "A") (pinfunction "A_A") (pintype "passive"))
      (node (ref "IC9") (pin "1") (pinfunction "SW_1") (pintype "output"))
      (node (ref "L1") (pin "2") (pinfunction "2_2") (pintype "passive"))
    )
    (net (code "118") (name "Net-(IC9-VIN)") (class "Default")
      (node (ref "IC9") (pin "5") (pinfunction "VIN_5") (pintype "input"))
      (node (ref "R23") (pin "2") (pinfunction "2_2") (pintype "passive"))
    )
    (net (code "119") (name "Net-(IC13-IO1)") (class "Default")
      (node (ref "IC13") (pin "1") (pinfunction "IO1_1") (pintype "bidirectional"))
      (node (ref "IC14") (pin "17") (pinfunction "TD+_17") (pintype "bidirectional"))
      (node (ref "R32") (pin "2") (pinfunction "2_2") (pintype "passive"))
      (node (ref "X5") (pin "1") (pinfunction "TD+_1") (pintype "input"))
    )
    (net (code "120") (name "Net-(IC13-IO2)") (class "Default")
      (node (ref "IC13") (pin "2") (pinfunction "IO2_2") (pintype "bidirectional"))
      (node (ref "IC14") (pin "16") (pinfunction "TD-_16") (pintype "bidirectional"))
      (node (ref "R33") (pin "1") (pinfunction "1_1") (pintype "passive"))
      (node (ref "X5") (pin "2") (pinfunction "TD-_2") (pintype "input"))
    )
    (net (code "121") (name "Net-(IC13-IO3)") (class "Default")
      (node (ref "IC13") (pin "4") (pinfunction "IO3_4") (pintype "bidirectional"))
      (node (ref "IC14") (pin "14") (pinfunction "RD+_14") (pintype "bidirectional"))
      (node (ref "R36") (pin "2") (pinfunction "2_2") (pintype "passive"))
      (node (ref "X5") (pin "7") (pinfunction "RD+_7") (pintype "input"))
    )
    (net (code "122") (name "Net-(IC13-IO4)") (class "Default")
      (node (ref "IC13") (pin "5") (pinfunction "IO4_5") (pintype "bidirectional"))
      (node (ref "IC14") (pin "13") (pinfunction "RD-_13") (pintype "bidirectional"))
      (node (ref "R41") (pin "1") (pinfunction "1_1") (pintype "passive"))
      (node (ref "X5") (pin "8") (pinfunction "RD-_8") (pintype "input"))
    )
    (net (code "123") (name "Net-(IC14-CRS{slash}CRS_DV{slash}LED_CFG)") (class "Default")
      (node (ref "IC14") (pin "40") (pinfunction "CRS/CRS_DV/LED_CFG_40") (pintype "output"))
      (node (ref "RN1") (pin "5") (pinfunction "2_5") (pintype "passive"))
    )
    (net (code "124") (name "Net-(IC14-MDIX_EN(RX_ER))") (class "Default")
      (node (ref "IC14") (pin "41") (pinfunction "MDIX_EN(RX_ER)_41") (pintype "output"))
      (node (ref "RN2") (pin "8") (pinfunction "2_8") (pintype "passive"))
    )
    (net (code "125") (name "Net-(IC14-MII_MODE(RX_DV))") (class "Default")
      (node (ref "IC14") (pin "39") (pinfunction "MII_MODE(RX_DV)_39") (pintype "output"))
      (node (ref "JP11") (pin "2") (pinfunction "2_2") (pintype "passive"))
      (node (ref "RN1") (pin "6") (pinfunction "2_6") (pintype "passive"))
    )
    (net (code "126") (name "Net-(IC14-PFBIN1)") (class "Default")
      (node (ref "C62") (pin "1") (pinfunction "1_1") (pintype "passive"))
      (node (ref "C63") (pin "1") (pinfunction "1_1") (pintype "passive"))
      (node (ref "C64") (pin "+") (pinfunction "+_+") (pintype "passive"))
      (node (ref "C65") (pin "1") (pinfunction "1_1") (pintype "passive"))
      (node (ref "IC14") (pin "18") (pinfunction "PFBIN1_18") (pintype "input"))
      (node (ref "IC14") (pin "23") (pinfunction "PFBOUT_23") (pintype "output"))
      (node (ref "IC14") (pin "37") (pinfunction "PFBIN2_37") (pintype "input"))
    )
    (net (code "127") (name "Net-(IC14-PHYAD0(COL))") (class "Default")
      (node (ref "IC14") (pin "42") (pinfunction "PHYAD0(COL)_42") (pintype "output"))
      (node (ref "RN2") (pin "7") (pinfunction "2_7") (pintype "passive"))
    )
    (net (code "128") (name "Net-(IC14-PHYAD1(RXD1_0))") (class "Default")
      (node (ref "IC14") (pin "43") (pinfunction "PHYAD1(RXD1_0)_43") (pintype "output"))
      (node (ref "RN2") (pin "6") (pinfunction "2_6") (pintype "passive"))
    )
    (net (code "129") (name "Net-(IC14-PHYAD2(RXD1_1))") (class "Default")
      (node (ref "IC14") (pin "44") (pinfunction "PHYAD2(RXD1_1)_44") (pintype "output"))
      (node (ref "RN2") (pin "5") (pinfunction "2_5") (pintype "passive"))
    )
    (net (code "130") (name "Net-(IC14-PHYAD3(RXD1_2))") (class "Default")
      (node (ref "IC14") (pin "45") (pinfunction "PHYAD3(RXD1_2)_45") (pintype "output"))
      (node (ref "RN3") (pin "8") (pinfunction "2_8") (pintype "passive"))
    )
    (net (code "131") (name "Net-(IC14-PHYAD4(RXD1_3))") (class "Default")
      (node (ref "IC14") (pin "46") (pinfunction "PHYAD4(RXD1_3)_46") (pintype "output"))
      (node (ref "RN3") (pin "7") (pinfunction "2_7") (pintype "passive"))
    )
    (net (code "132") (name "Net-(IC14-PWR_DOWN{slash}INT)") (class "Default")
      (node (ref "IC14") (pin "7") (pinfunction "PWR_DOWN/INT_7") (pintype "input"))
      (node (ref "JP13") (pin "2") (pinfunction "2_2") (pintype "passive"))
    )
    (net (code "133") (name "Net-(IC14-RBIAS)") (class "Default")
      (node (ref "IC14") (pin "24") (pinfunction "RBIAS_24") (pintype "input"))
      (node (ref "R47") (pin "2") (pinfunction "2_2") (pintype "passive"))
    )
    (net (code "134") (name "Net-(IC14-RESERVED-20)") (class "Default")
      (node (ref "IC14") (pin "20") (pinfunction "RESERVED-20_20") (pintype "bidirectional"))
      (node (ref "R46") (pin "2") (pinfunction "2_2") (pintype "passive"))
    )
    (net (code "135") (name "Net-(IC14-RESERVED-21)") (class "Default")
      (node (ref "IC14") (pin "21") (pinfunction "RESERVED-21_21") (pintype "bidirectional"))
      (node (ref "R45") (pin "2") (pinfunction "2_2") (pintype "passive"))
    )
    (net (code "136") (name "Net-(IC14-RX_CLK)") (class "Default")
      (node (ref "IC14") (pin "38") (pinfunction "RX_CLK_38") (pintype "output"))
      (node (ref "RN1") (pin "7") (pinfunction "2_7") (pintype "passive"))
    )
    (net (code "137") (name "Net-(IC14-TXD_0)") (class "Default")
      (node (ref "IC14") (pin "3") (pinfunction "TXD_0_3") (pintype "input"))
      (node (ref "RN4") (pin "8") (pinfunction "2_8") (pintype "passive"))
    )
    (net (code "138") (name "Net-(IC14-TXD_1)") (class "Default")
      (node (ref "IC14") (pin "4") (pinfunction "TXD_1_4") (pintype "input"))
      (node (ref "RN4") (pin "7") (pinfunction "2_7") (pintype "passive"))
    )
    (net (code "139") (name "Net-(IC14-TXD_2)") (class "Default")
      (node (ref "IC14") (pin "5") (pinfunction "TXD_2_5") (pintype "input"))
      (node (ref "RN4") (pin "6") (pinfunction "2_6") (pintype "passive"))
    )
    (net (code "140") (name "Net-(IC14-TXD_3{slash}SNI_MODE)") (class "Default")
      (node (ref "IC14") (pin "6") (pinfunction "TXD_3/SNI_MODE_6") (pintype "input"))
      (node (ref "RN4") (pin "5") (pinfunction "2_5") (pintype "passive"))
    )
    (net (code "141") (name "Net-(IC14-TX_CLK)") (class "Default")
      (node (ref "IC14") (pin "1") (pinfunction "TX_CLK_1") (pintype "output"))
      (node (ref "RN3") (pin "6") (pinfunction "2_6") (pintype "passive"))
    )
    (net (code "142") (name "Net-(IC14-TX_EN)") (class "Default")
      (node (ref "IC14") (pin "2") (pinfunction "TX_EN_2") (pintype "input"))
      (node (ref "RN3") (pin "5") (pinfunction "2_5") (pintype "passive"))
    )
    (net (code "143") (name "Net-(IC14-X1)") (class "Default")
      (node (ref "IC14") (pin "34") (pinfunction "X1_34") (pintype "input"))
      (node (ref "RN1") (pin "8") (pinfunction "2_8") (pintype "passive"))
    )
    (net (code "144") (name "Net-(JP9-Pad2)") (class "Default")
      (node (ref "JP9") (pin "2") (pinfunction "2_2") (pintype "passive"))
      (node (ref "R37") (pin "2") (pinfunction "2_2") (pintype "passive"))
    )
    (net (code "145") (name "Net-(JP10-Pad1)") (class "Default")
      (node (ref "JP10") (pin "1") (pinfunction "1_1") (pintype "passive"))
      (node (ref "JP12") (pin "1") (pinfunction "1_1") (pintype "passive"))
      (node (ref "RN2") (pin "1") (pinfunction "1_1") (pintype "passive"))
    )
    (net (code "146") (name "Net-(JP10-Pad2)") (class "Default")
      (node (ref "JP10") (pin "2") (pinfunction "2_2") (pintype "passive"))
      (node (ref "R34") (pin "2") (pinfunction "2_2") (pintype "passive"))
    )
    (net (code "147") (name "Net-(JP11-Pad1)") (class "Default")
      (node (ref "JP11") (pin "1") (pinfunction "1_1") (pintype "passive"))
      (node (ref "R39") (pin "2") (pinfunction "2_2") (pintype "passive"))
    )
    (net (code "148") (name "Net-(JP13-Pad1)") (class "Default")
      (node (ref "JP13") (pin "1") (pinfunction "1_1") (pintype "passive"))
      (node (ref "R48") (pin "2") (pinfunction "2_2") (pintype "passive"))
    )
    (net (code "149") (name "Net-(LCD1-B0)") (class "Default")
      (node (ref "JP6") (pin "COM") (pinfunction "COM_COM") (pintype "passive"))
      (node (ref "LCD1") (pin "13") (pinfunction "G0_13") (pintype "input"))
      (node (ref "LCD1") (pin "14") (pinfunction "G1_14") (pintype "input"))
      (node (ref "LCD1") (pin "21") (pinfunction "B0_21") (pintype "input"))
      (node (ref "LCD1") (pin "22") (pinfunction "B1_22") (pintype "input"))
      (node (ref "LCD1") (pin "23") (pinfunction "B2_23") (pintype "input"))
      (node (ref "LCD1") (pin "5") (pinfunction "R0_5") (pintype "input"))
      (node (ref "LCD1") (pin "6") (pinfunction "R1_6") (pintype "input"))
      (node (ref "LCD1") (pin "7") (pinfunction "R2_7") (pintype "input"))
    )
    (net (code "150") (name "Net-(LCD1-RESET)") (class "Default")
      (node (ref "JP7") (pin "COM") (pinfunction "COM_COM") (pintype "passive"))
      (node (ref "LCD1") (pin "36") (pinfunction "RESET_36") (pintype "input"))
    )
    (net (code "151") (name "Net-(Q1-PadB)") (class "Default")
      (node (ref "Q1") (pin "B") (pinfunction "B_B") (pintype "passive"))
      (node (ref "R27") (pin "2") (pinfunction "2_2") (pintype "passive"))
    )
    (net (code "152") (name "Net-(Q1-PadC)") (class "Default")
      (node (ref "Q1") (pin "C") (pinfunction "C_C") (pintype "passive"))
      (node (ref "R24") (pin "1") (pinfunction "1_1") (pintype "passive"))
    )
    (net (code "153") (name "Net-(Q2-D)") (class "Default")
      (node (ref "Q2") (pin "3") (pinfunction "D_3") (pintype "passive"))
      (node (ref "SP1") (pin "-B") (pinfunction "-_-B") (pintype "passive"))
      (node (ref "SP1") (pin "-B.1") (pinfunction "-_-B.1") (pintype "passive"))
    )
    (net (code "154") (name "Net-(R1-Pad2)") (class "Default")
      (node (ref "R1") (pin "2") (pinfunction "2_2") (pintype "passive"))
      (node (ref "R2") (pin "2") (pinfunction "2_2") (pintype "passive"))
      (node (ref "SW2") (pin "A") (pinfunction "A_A") (pintype "passive"))
    )
    (net (code "155") (name "Net-(R3-Pad2)") (class "Default")
      (node (ref "R3") (pin "2") (pinfunction "2_2") (pintype "passive"))
      (node (ref "R4") (pin "1") (pinfunction "1_1") (pintype "passive"))
    )
    (net (code "156") (name "Net-(R7-Pad2)") (class "Default")
      (node (ref "R7") (pin "2") (pinfunction "2_2") (pintype "passive"))
      (node (ref "R8") (pin "1") (pinfunction "1_1") (pintype "passive"))
    )
    (net (code "157") (name "Net-(R10-Pad2)") (class "Default")
      (node (ref "R10") (pin "2") (pinfunction "2_2") (pintype "passive"))
      (node (ref "R6") (pin "2") (pinfunction "2_2") (pintype "passive"))
      (node (ref "SW2") (pin "B") (pinfunction "B_B") (pintype "passive"))
    )
    (net (code "158") (name "Net-(R24-Pad2)") (class "Default")
      (node (ref "R24") (pin "2") (pinfunction "2_2") (pintype "passive"))
      (node (ref "VBUS") (pin "C") (pinfunction "C_C") (pintype "passive"))
    )
    (net (code "159") (name "Net-(R38-Pad2)") (class "Default")
      (node (ref "R38") (pin "2") (pinfunction "2_2") (pintype "passive"))
      (node (ref "SPEED") (pin "A") (pinfunction "A_A") (pintype "passive"))
    )
    (net (code "160") (name "Net-(X2E-1)") (class "Default")
      (node (ref "SCL") (pin "2") (pinfunction "2_2") (pintype "passive"))
      (node (ref "X2") (pin "13") (pinfunction "1_13") (pintype "passive"))
    )
    (net (code "161") (name "Net-(X2F-1)") (class "Default")
      (node (ref "SDA") (pin "1") (pinfunction "1_1") (pintype "passive"))
      (node (ref "X2") (pin "14") (pinfunction "1_14") (pintype "passive"))
    )
    (net (code "162") (name "Net-(X4A-S)") (class "Default")
      (node (ref "JP5") (pin "2") (pinfunction "2_2") (pintype "passive"))
      (node (ref "R18") (pin "2") (pinfunction "2_2") (pintype "passive"))
      (node (ref "X4") (pin "1") (pinfunction "S_1") (pintype "passive"))
    )
    (net (code "163") (name "Net-(X5-GREEN-C)") (class "Default")
      (node (ref "R44") (pin "1") (pinfunction "1_1") (pintype "passive"))
      (node (ref "X5") (pin "10") (pinfunction "GREEN-C_10") (pintype "passive"))
    )
    (net (code "164") (name "Net-(X5-YELLOW-C)") (class "Default")
      (node (ref "R43") (pin "1") (pinfunction "1_1") (pintype "passive"))
      (node (ref "X5") (pin "11") (pinfunction "YELLOW-C_11") (pintype "passive"))
    )
    (net (code "165") (name "OE_SYNC") (class "Default")
      (node (ref "IC3") (pin "94") (pinfunction "PD13_94") (pintype "bidirectional"))
      (node (ref "X1") (pin "10") (pinfunction "1_10") (pintype "passive"))
    )
    (net (code "166") (name "PE") (class "Default")
      (node (ref "C1") (pin "1") (pinfunction "1_1") (pintype "passive"))
      (node (ref "C51") (pin "1") (pinfunction "1_1") (pintype "passive"))
      (node (ref "J2") (pin "SH1") (pinfunction "SH1_SH1") (pintype "bidirectional"))
      (node (ref "J2") (pin "SH1.1") (pinfunction "SH1_SH1.1") (pintype "bidirectional"))
      (node (ref "J2") (pin "SH2") (pinfunction "SH2_SH2") (pintype "bidirectional"))
      (node (ref "J2") (pin "SH2.2") (pinfunction "SH2_SH2.2") (pintype "bidirectional"))
      (node (ref "JP1") (pin "2") (pinfunction "2_2") (pintype "passive"))
      (node (ref "X2") (pin "1") (pinfunction "1_1") (pintype "passive"))
      (node (ref "X5") (pin "SH") (pinfunction "SH_SH") (pintype "passive"))
      (node (ref "X5") (pin "SH2") (pinfunction "SH_SH2") (pintype "passive"))
    )
    (net (code "167") (name "PWR_DIRECT") (class "Default")
      (node (ref "IC3") (pin "110") (pinfunction "PG2_110") (pintype "bidirectional"))
      (node (ref "X2") (pin "12") (pinfunction "1_12") (pintype "passive"))
    )
    (net (code "168") (name "PWR_SSTART") (class "Default")
      (node (ref "IC3") (pin "111") (pinfunction "PG3_111") (pintype "bidirectional"))
      (node (ref "X2") (pin "11") (pinfunction "1_11") (pintype "passive"))
    )
    (net (code "169") (name "RCC_OSC32_IN") (class "Default")
      (node (ref "C10") (pin "1") (pinfunction "1_1") (pintype "passive"))
      (node (ref "IC3") (pin "9") (pinfunction "PC14_9") (pintype "bidirectional"))
      (node (ref "Y2") (pin "1") (pinfunction "1_1") (pintype "passive"))
    )
    (net (code "170") (name "RCC_OSC32_OUT") (class "Default")
      (node (ref "C12") (pin "1") (pinfunction "1_1") (pintype "passive"))
      (node (ref "IC3") (pin "10") (pinfunction "PC15_10") (pintype "bidirectional"))
      (node (ref "Y2") (pin "4") (pinfunction "2_4") (pintype "passive"))
    )
    (net (code "171") (name "RCC_OSC_IN") (class "Default")
      (node (ref "C9") (pin "2") (pinfunction "2_2") (pintype "passive"))
      (node (ref "IC3") (pin "29") (pinfunction "PH0_29") (pintype "bidirectional"))
      (node (ref "Y1") (pin "2") (pinfunction "2_2") (pintype "passive"))
    )
    (net (code "172") (name "RCC_OSC_OUT") (class "Default")
      (node (ref "C11") (pin "2") (pinfunction "2_2") (pintype "passive"))
      (node (ref "IC3") (pin "30") (pinfunction "PH1_30") (pintype "bidirectional"))
      (node (ref "Y1") (pin "1") (pinfunction "1_1") (pintype "passive"))
    )
    (net (code "173") (name "SDMMC1_CK") (class "Default")
      (node (ref "IC3") (pin "141") (pinfunction "PC12_141") (pintype "bidirectional"))
      (node (ref "J1") (pin "5") (pinfunction "CLK_5") (pintype "passive"))
    )
    (net (code "174") (name "SDMMC1_CMD") (class "Default")
      (node (ref "IC3") (pin "144") (pinfunction "PD2_144") (pintype "bidirectional"))
      (node (ref "J1") (pin "3") (pinfunction "CMD_3") (pintype "passive"))
      (node (ref "R22") (pin "2") (pinfunction "2_2") (pintype "passive"))
    )
    (net (code "175") (name "SDMMC1_D0") (class "Default")
      (node (ref "IC3") (pin "121") (pinfunction "PC8_121") (pintype "bidirectional"))
      (node (ref "J1") (pin "7") (pinfunction "DAT0_7") (pintype "passive"))
      (node (ref "R21") (pin "2") (pinfunction "2_2") (pintype "passive"))
    )
    (net (code "176") (name "SD_DETECT") (class "Default")
      (node (ref "IC3") (pin "140") (pinfunction "PC11_140") (pintype "bidirectional"))
      (node (ref "J1") (pin "SW1") (pinfunction "SW1_SW1") (pintype "passive"))
    )
    (net (code "177") (name "SPI2_CLK") (class "Default")
      (node (ref "IC3") (pin "133") (pinfunction "PI1_133") (pintype "bidirectional"))
      (node (ref "X1") (pin "32") (pinfunction "1_32") (pintype "passive"))
    )
    (net (code "178") (name "SPI2_CSA") (class "Default")
      (node (ref "IC3") (pin "93") (pinfunction "PD12_93") (pintype "bidirectional"))
      (node (ref "X1") (pin "28") (pinfunction "1_28") (pintype "passive"))
    )
    (net (code "179") (name "SPI2_CSB") (class "Default")
      (node (ref "IC3") (pin "92") (pinfunction "PD11_92") (pintype "bidirectional"))
      (node (ref "X1") (pin "27") (pinfunction "1_27") (pintype "passive"))
    )
    (net (code "180") (name "SPI2_IRQ") (class "Default")
      (node (ref "IC3") (pin "123") (pinfunction "PA8_123") (pintype "bidirectional"))
      (node (ref "X1") (pin "25") (pinfunction "1_25") (pintype "passive"))
    )
    (net (code "181") (name "SPI2_MISO") (class "Default")
      (node (ref "IC3") (pin "87") (pinfunction "PB14_87") (pintype "bidirectional"))
      (node (ref "X1") (pin "31") (pinfunction "1_31") (pintype "passive"))
    )
    (net (code "182") (name "SPI2_MOSI") (class "Default")
      (node (ref "IC3") (pin "134") (pinfunction "PI3_134") (pintype "bidirectional"))
      (node (ref "X1") (pin "33") (pinfunction "1_33") (pintype "passive"))
    )
    (net (code "183") (name "SPI4_CLK") (class "Default")
      (node (ref "IC3") (pin "1") (pinfunction "PE2_1") (pintype "bidirectional"))
      (node (ref "X1") (pin "23") (pinfunction "1_23") (pintype "passive"))
    )
    (net (code "184") (name "SPI4_CSA") (class "Default")
      (node (ref "IC3") (pin "2") (pinfunction "PE3_2") (pintype "bidirectional"))
      (node (ref "X1") (pin "22") (pinfunction "1_22") (pintype "passive"))
    )
    (net (code "185") (name "SPI4_CSB") (class "Default")
      (node (ref "IC3") (pin "3") (pinfunction "PE4_3") (pintype "bidirectional"))
      (node (ref "X1") (pin "21") (pinfunction "1_21") (pintype "passive"))
    )
    (net (code "186") (name "SPI4_IRQ") (class "Default")
      (node (ref "IC3") (pin "168") (pinfunction "PB9_168") (pintype "bidirectional"))
      (node (ref "X1") (pin "19") (pinfunction "1_19") (pintype "passive"))
    )
    (net (code "187") (name "SPI4_MISO") (class "Default")
      (node (ref "IC3") (pin "4") (pinfunction "PE5_4") (pintype "bidirectional"))
      (node (ref "X1") (pin "24") (pinfunction "1_24") (pintype "passive"))
    )
    (net (code "188") (name "SPI4_MOSI") (class "Default")
      (node (ref "IC3") (pin "5") (pinfunction "PE6_5") (pintype "bidirectional"))
      (node (ref "X1") (pin "26") (pinfunction "1_26") (pintype "passive"))
    )
    (net (code "189") (name "SPI5_CLK") (class "Default")
      (node (ref "IC3") (pin "25") (pinfunction "PF7_25") (pintype "bidirectional"))
      (node (ref "X1") (pin "17") (pinfunction "1_17") (pintype "passive"))
    )
    (net (code "190") (name "SPI5_CSA") (class "Default")
      (node (ref "IC3") (pin "157") (pinfunction "PG14_157") (pintype "bidirectional"))
      (node (ref "X1") (pin "11") (pinfunction "1_11") (pintype "passive"))
    )
    (net (code "191") (name "SPI5_CSB") (class "Default")
      (node (ref "IC3") (pin "156") (pinfunction "PG13_156") (pintype "bidirectional"))
      (node (ref "X1") (pin "13") (pinfunction "1_13") (pintype "passive"))
    )
    (net (code "192") (name "SPI5_IRQ") (class "Default")
      (node (ref "IC3") (pin "138") (pinfunction "PA15_138") (pintype "bidirectional"))
      (node (ref "X1") (pin "9") (pinfunction "1_9") (pintype "passive"))
    )
    (net (code "193") (name "SPI5_MISO") (class "Default")
      (node (ref "IC3") (pin "26") (pinfunction "PF8_26") (pintype "bidirectional"))
      (node (ref "X1") (pin "18") (pinfunction "1_18") (pintype "passive"))
    )
    (net (code "194") (name "SPI5_MOSI") (class "Default")
      (node (ref "IC3") (pin "27") (pinfunction "PF9_27") (pintype "bidirectional"))
      (node (ref "X1") (pin "20") (pinfunction "1_20") (pintype "passive"))
    )
    (net (code "195") (name "SYS_JTCK-SWCLK") (class "Default")
      (node (ref "IC3") (pin "137") (pinfunction "PA14_137") (pintype "bidirectional"))
      (node (ref "R20") (pin "1") (pinfunction "1_1") (pintype "passive"))
    )
    (net (code "196") (name "SYS_JTDO-SWO") (class "Default")
      (node (ref "IC3") (pin "161") (pinfunction "PB3_161") (pintype "bidirectional"))
      (node (ref "IC5") (pin "5") (pinfunction "IO4_5") (pintype "bidirectional"))
      (node (ref "X4") (pin "6") (pinfunction "S_6") (pintype "passive"))
    )
    (net (code "197") (name "SYS_JTMS-SWDIO") (class "Default")
      (node (ref "IC3") (pin "128") (pinfunction "PA13_128") (pintype "bidirectional"))
      (node (ref "R19") (pin "1") (pinfunction "1_1") (pintype "passive"))
    )
    (net (code "198") (name "TCK") (class "Default")
      (node (ref "IC5") (pin "1") (pinfunction "IO1_1") (pintype "bidirectional"))
      (node (ref "R20") (pin "2") (pinfunction "2_2") (pintype "passive"))
      (node (ref "X4") (pin "2") (pinfunction "S_2") (pintype "passive"))
    )
    (net (code "199") (name "TFT_BRIGHTNESS") (class "Default")
      (node (ref "IC3") (pin "88") (pinfunction "PB15_88") (pintype "bidirectional"))
      (node (ref "IC9") (pin "4") (pinfunction "CTRL_4") (pintype "input"))
    )
    (net (code "200") (name "TMS") (class "Default")
      (node (ref "IC5") (pin "2") (pinfunction "IO2_2") (pintype "bidirectional"))
      (node (ref "R19") (pin "2") (pinfunction "2_2") (pintype "passive"))
      (node (ref "X4") (pin "4") (pinfunction "S_4") (pintype "passive"))
    )
    (net (code "201") (name "UART_RX{slash}DIN1") (class "Default")
      (node (ref "IC3") (pin "24") (pinfunction "PF6_24") (pintype "bidirectional"))
      (node (ref "R5") (pin "2") (pinfunction "2_2") (pintype "passive"))
      (node (ref "X1") (pin "3") (pinfunction "1_3") (pintype "passive"))
    )
    (net (code "202") (name "UART_TX{slash}DOUT1") (class "Default")
      (node (ref "IC2") (pin "11") (pinfunction "I_11") (pintype "input"))
      (node (ref "IC2") (pin "5") (pinfunction "I_5") (pintype "input"))
      (node (ref "IC3") (pin "162") (pinfunction "PB4_162") (pintype "bidirectional"))
      (node (ref "X1") (pin "4") (pinfunction "1_4") (pintype "passive"))
    )
    (net (code "203") (name "USB_D_N") (class "Default")
      (node (ref "IC10") (pin "1") (pinfunction "IO1_1") (pintype "bidirectional"))
      (node (ref "J2") (pin "2") (pinfunction "D-_2") (pintype "passive"))
      (node (ref "R28") (pin "1") (pinfunction "1_1") (pintype "passive"))
    )
    (net (code "204") (name "USB_D_P") (class "Default")
      (node (ref "IC10") (pin "2") (pinfunction "IO2_2") (pintype "bidirectional"))
      (node (ref "J2") (pin "3") (pinfunction "D+_3") (pintype "passive"))
      (node (ref "R29") (pin "1") (pinfunction "1_1") (pintype "passive"))
    )
    (net (code "205") (name "USB_OTG_FS_D_N") (class "Default")
      (node (ref "IC3") (pin "126") (pinfunction "PA11_126") (pintype "bidirectional"))
      (node (ref "R28") (pin "2") (pinfunction "2_2") (pintype "passive"))
    )
    (net (code "206") (name "USB_OTG_FS_D_P") (class "Default")
      (node (ref "IC3") (pin "127") (pinfunction "PA12_127") (pintype "bidirectional"))
      (node (ref "R29") (pin "2") (pinfunction "2_2") (pintype "passive"))
    )
    (net (code "207") (name "USB_OTG_FS_ID") (class "Default")
      (node (ref "IC10") (pin "4") (pinfunction "IO3_4") (pintype "bidirectional"))
      (node (ref "IC3") (pin "125") (pinfunction "PA10_125") (pintype "bidirectional"))
      (node (ref "J2") (pin "4") (pinfunction "ID_4") (pintype "passive"))
    )
    (net (code "208") (name "USB_OTG_FS_PSO") (class "Default")
      (node (ref "IC3") (pin "147") (pinfunction "PD5_147") (pintype "bidirectional"))
      (node (ref "IC8") (pin "4") (pinfunction "EN_4") (pintype "input"))
    )
    (net (code "209") (name "USB_OTG_FS_VBUS") (class "Default")
      (node (ref "C49") (pin "+") (pinfunction "+_+") (pintype "passive"))
      (node (ref "C52") (pin "2") (pinfunction "2_2") (pintype "passive"))
      (node (ref "IC10") (pin "6") (pinfunction "VCC_6") (pintype "passive"))
      (node (ref "IC3") (pin "124") (pinfunction "PA9_124") (pintype "bidirectional"))
      (node (ref "IC8") (pin "1") (pinfunction "OUT_1") (pintype "output"))
      (node (ref "J2") (pin "1") (pinfunction "VCC_1") (pintype "passive"))
      (node (ref "R27") (pin "1") (pinfunction "1_1") (pintype "passive"))
    )
    (net (code "210") (name "USER_SW") (class "Default")
      (node (ref "C4") (pin "2") (pinfunction "2_2") (pintype "passive"))
      (node (ref "IC3") (pin "152") (pinfunction "PG9_152") (pintype "bidirectional"))
      (node (ref "SW1") (pin "1") (pinfunction "1_1") (pintype "passive"))
    )
    (net (code "211") (name "VBAT") (class "Default")
      (node (ref "IC3") (pin "6") (pinfunction "VBAT_6") (pintype "power_in"))
      (node (ref "JP4") (pin "COM") (pinfunction "COM_COM") (pintype "passive"))
    )
    (net (code "212") (name "VCAP1") (class "Default")
      (node (ref "C37") (pin "1") (pinfunction "1_1") (pintype "passive"))
      (node (ref "IC3") (pin "81") (pinfunction "VCAP_1_81") (pintype "power_in"))
    )
    (net (code "213") (name "VCAP2") (class "Default")
      (node (ref "C36") (pin "1") (pinfunction "1_1") (pintype "passive"))
      (node (ref "IC3") (pin "129") (pinfunction "VCAP_2_129") (pintype "power_in"))
    )
    (net (code "214") (name "VDD") (class "Default")
      (node (ref "C16") (pin "1") (pinfunction "1_1") (pintype "passive"))
      (node (ref "C17") (pin "1") (pinfunction "1_1") (pintype "passive"))
      (node (ref "C18") (pin "1") (pinfunction "1_1") (pintype "passive"))
      (node (ref "C19") (pin "1") (pinfunction "1_1") (pintype "passive"))
      (node (ref "C20") (pin "1") (pinfunction "1_1") (pintype "passive"))
      (node (ref "C21") (pin "1") (pinfunction "1_1") (pintype "passive"))
      (node (ref "C22") (pin "+") (pinfunction "+_+") (pintype "passive"))
      (node (ref "C23") (pin "1") (pinfunction "1_1") (pintype "passive"))
      (node (ref "C24") (pin "1") (pinfunction "1_1") (pintype "passive"))
      (node (ref "C25") (pin "1") (pinfunction "1_1") (pintype "passive"))
      (node (ref "C26") (pin "1") (pinfunction "1_1") (pintype "passive"))
      (node (ref "C27") (pin "1") (pinfunction "1_1") (pintype "passive"))
      (node (ref "C28") (pin "1") (pinfunction "1_1") (pintype "passive"))
      (node (ref "C29") (pin "1") (pinfunction "1_1") (pintype "passive"))
      (node (ref "C30") (pin "1") (pinfunction "1_1") (pintype "passive"))
      (node (ref "C31") (pin "1") (pinfunction "1_1") (pintype "passive"))
      (node (ref "C32") (pin "1") (pinfunction "1_1") (pintype "passive"))
      (node (ref "C33") (pin "1") (pinfunction "1_1") (pintype "passive"))
      (node (ref "C8") (pin "2") (pinfunction "2_2") (pintype "passive"))
      (node (ref "FB1") (pin "P$1") (pinfunction "1_P$1") (pintype "passive"))
      (node (ref "IC3") (pin "118") (pinfunction "VDDUSB_118") (pintype "power_in"))
      (node (ref "IC3") (pin "131") (pinfunction "VDD_10_131") (pintype "power_in"))
      (node (ref "IC3") (pin "136") (pinfunction "VDD_11_136") (pintype "power_in"))
      (node (ref "IC3") (pin "149") (pinfunction "VDDSDMMC_149") (pintype "power_in"))
      (node (ref "IC3") (pin "15") (pinfunction "VDD_2_15") (pintype "power_in"))
      (node (ref "IC3") (pin "159") (pinfunction "VDD_12_159") (pintype "power_in"))
      (node (ref "IC3") (pin "171") (pinfunction "PDR_ON_171") (pintype "passive"))
      (node (ref "IC3") (pin "172") (pinfunction "VDD_172") (pintype "power_in"))
      (node (ref "IC3") (pin "23") (pinfunction "VDD_3_23") (pintype "power_in"))
      (node (ref "IC3") (pin "36") (pinfunction "VDD_4_36") (pintype "power_in"))
      (node (ref "IC3") (pin "49") (pinfunction "VDD_5_49") (pintype "power_in"))
      (node (ref "IC3") (pin "62") (pinfunction "VDD_6_62") (pintype "power_in"))
      (node (ref "IC3") (pin "72") (pinfunction "VDD_7_72") (pintype "power_in"))
      (node (ref "IC3") (pin "82") (pinfunction "VDD_8_82") (pintype "power_in"))
      (node (ref "IC3") (pin "96") (pinfunction "VDD_9_96") (pintype "power_in"))
      (node (ref "IC3") (pin "99") (pinfunction "VDDDSI_99") (pintype "power_in"))
      (node (ref "JP2") (pin "1") (pinfunction "1_1") (pintype "passive"))
      (node (ref "JP4") (pin "NO") (pinfunction "NO_NO") (pintype "passive"))
      (node (ref "R11") (pin "1") (pinfunction "1_1") (pintype "passive"))
    )
    (net (code "215") (name "VDDA") (class "Default")
      (node (ref "C34") (pin "1") (pinfunction "1_1") (pintype "passive"))
      (node (ref "C35") (pin "1") (pinfunction "1_1") (pintype "passive"))
      (node (ref "FB1") (pin "P$2") (pinfunction "2_P$2") (pintype "passive"))
      (node (ref "IC3") (pin "39") (pinfunction "VDDA_39") (pintype "power_in"))
      (node (ref "R17") (pin "2") (pinfunction "2_2") (pintype "passive"))
    )
    (net (code "216") (name "VLED+") (class "Default")
      (node (ref "C48") (pin "1") (pinfunction "1_1") (pintype "passive"))
      (node (ref "D2") (pin "C") (pinfunction "C_C") (pintype "passive"))
      (node (ref "LCD1") (pin "2") (pinfunction "VLED+_2") (pintype "power_in"))
      (node (ref "ZD1") (pin "C") (pinfunction "C_C") (pintype "passive"))
    )
    (net (code "217") (name "VLED-") (class "Default")
      (node (ref "IC9") (pin "3") (pinfunction "FB_3") (pintype "input"))
      (node (ref "LCD1") (pin "1") (pinfunction "VLED-_1") (pintype "power_in"))
      (node (ref "R25") (pin "1") (pinfunction "1_1") (pintype "passive"))
      (node (ref "ZD1") (pin "A") (pinfunction "A_A") (pintype "passive"))
    )
    (net (code "218") (name "VREF+") (class "Default")
      (node (ref "IC3") (pin "38") (pinfunction "VREF+_38") (pintype "power_in"))
      (node (ref "R17") (pin "1") (pinfunction "1_1") (pintype "passive"))
    )
    (net (code "219") (name "XL") (class "Default")
      (node (ref "IC11") (pin "4") (pinfunction "IO3_4") (pintype "bidirectional"))
      (node (ref "IC12") (pin "4") (pinfunction "X-_4") (pintype "input"))
      (node (ref "LCD1") (pin "39") (pinfunction "XL_39") (pintype "passive"))
    )
    (net (code "220") (name "XR") (class "Default")
      (node (ref "IC11") (pin "1") (pinfunction "IO1_1") (pintype "bidirectional"))
      (node (ref "IC12") (pin "2") (pinfunction "X+_2") (pintype "input"))
      (node (ref "LCD1") (pin "37") (pinfunction "XR_37") (pintype "passive"))
    )
    (net (code "221") (name "YD") (class "Default")
      (node (ref "IC11") (pin "2") (pinfunction "IO2_2") (pintype "bidirectional"))
      (node (ref "IC12") (pin "5") (pinfunction "Y-_5") (pintype "input"))
      (node (ref "LCD1") (pin "38") (pinfunction "YD_38") (pintype "passive"))
    )
    (net (code "222") (name "YU") (class "Default")
      (node (ref "IC11") (pin "5") (pinfunction "IO4_5") (pintype "bidirectional"))
      (node (ref "IC12") (pin "3") (pinfunction "Y+_3") (pintype "input"))
      (node (ref "LCD1") (pin "40") (pinfunction "YU_40") (pintype "passive"))
    )
    (net (code "223") (name "unconnected-(IC3A-PC10-Pad139)") (class "Default")
      (node (ref "IC3") (pin "139") (pinfunction "PC10_139") (pintype "bidirectional"))
    )
    (net (code "224") (name "unconnected-(IC3A-PD6-Pad150)") (class "Default")
      (node (ref "IC3") (pin "150") (pinfunction "PD6_150") (pintype "bidirectional"))
    )
    (net (code "225") (name "unconnected-(IC3C-DSI_CKN-Pad105)") (class "Default")
      (node (ref "IC3") (pin "105") (pinfunction "DSI_CKN_105") (pintype "bidirectional"))
    )
    (net (code "226") (name "unconnected-(IC3C-DSI_CKP-Pad104)") (class "Default")
      (node (ref "IC3") (pin "104") (pinfunction "DSI_CKP_104") (pintype "bidirectional"))
    )
    (net (code "227") (name "unconnected-(IC3C-DSI_D0N-Pad102)") (class "Default")
      (node (ref "IC3") (pin "102") (pinfunction "DSI_D0N_102") (pintype "bidirectional"))
    )
    (net (code "228") (name "unconnected-(IC3C-DSI_D0P-Pad101)") (class "Default")
      (node (ref "IC3") (pin "101") (pinfunction "DSI_D0P_101") (pintype "bidirectional"))
    )
    (net (code "229") (name "unconnected-(IC3C-DSI_D1N-Pad108)") (class "Default")
      (node (ref "IC3") (pin "108") (pinfunction "DSI_D1N_108") (pintype "bidirectional"))
    )
    (net (code "230") (name "unconnected-(IC3C-DSI_D1P-Pad107)") (class "Default")
      (node (ref "IC3") (pin "107") (pinfunction "DSI_D1P_107") (pintype "bidirectional"))
    )
    (net (code "231") (name "unconnected-(IC3C-PI8-Pad7)") (class "Default")
      (node (ref "IC3") (pin "7") (pinfunction "PI8_7") (pintype "bidirectional"))
    )
    (net (code "232") (name "unconnected-(IC6-A12{slash}NC-36-Pad36)") (class "Default")
      (node (ref "IC6") (pin "36") (pinfunction "A12/NC-36_36") (pintype "passive"))
    )
    (net (code "233") (name "unconnected-(IC6-NC-40-Pad40)") (class "Default")
      (node (ref "IC6") (pin "40") (pinfunction "NC-40_40") (pintype "no_connect"))
    )
    (net (code "234") (name "unconnected-(IC10-IO4-Pad5)") (class "Default")
      (node (ref "IC10") (pin "5") (pinfunction "IO4_5") (pintype "bidirectional"))
    )
    (net (code "235") (name "unconnected-(IC12-AUX-Pad16)") (class "Default")
      (node (ref "IC12") (pin "16") (pinfunction "AUX_16") (pintype "input"))
    )
    (net (code "236") (name "unconnected-(IC14-CLK_OUT-Pad25)") (class "Default")
      (node (ref "IC14") (pin "25") (pinfunction "CLK_OUT_25") (pintype "output"))
    )
    (net (code "237") (name "unconnected-(IC14-TCK-Pad8)") (class "Default")
      (node (ref "IC14") (pin "8") (pinfunction "TCK_8") (pintype "input"))
    )
    (net (code "238") (name "unconnected-(IC14-TDI-Pad12)") (class "Default")
      (node (ref "IC14") (pin "12") (pinfunction "TDI_12") (pintype "input"))
    )
    (net (code "239") (name "unconnected-(IC14-TDO-Pad9)") (class "Default")
      (node (ref "IC14") (pin "9") (pinfunction "TDO_9") (pintype "output"))
    )
    (net (code "240") (name "unconnected-(IC14-TMS-Pad10)") (class "Default")
      (node (ref "IC14") (pin "10") (pinfunction "TMS_10") (pintype "input"))
    )
    (net (code "241") (name "unconnected-(IC14-X2-Pad33)") (class "Default")
      (node (ref "IC14") (pin "33") (pinfunction "X2_33") (pintype "output"))
    )
    (net (code "242") (name "unconnected-(IC14-~{TRST}-Pad11)") (class "Default")
      (node (ref "IC14") (pin "11") (pinfunction "~{TRST}_11") (pintype "input"))
    )
    (net (code "243") (name "unconnected-(J1-CD{slash}DAT3-Pad2)") (class "Default")
      (node (ref "J1") (pin "2") (pinfunction "CD/DAT3_2") (pintype "passive"))
    )
    (net (code "244") (name "unconnected-(J1-DAT1-Pad8)") (class "Default")
      (node (ref "J1") (pin "8") (pinfunction "DAT1_8") (pintype "passive"))
    )
    (net (code "245") (name "unconnected-(J1-DAT2-Pad1)") (class "Default")
      (node (ref "J1") (pin "1") (pinfunction "DAT2_1") (pintype "passive"))
    )
    (net (code "246") (name "unconnected-(LCD1-NC1-Pad35)") (class "Default")
      (node (ref "LCD1") (pin "35") (pinfunction "NC1_35") (pintype "no_connect"))
    )
    (net (code "247") (name "~{FAULT}") (class "Default")
      (node (ref "IC3") (pin "58") (pinfunction "PB2_58") (pintype "bidirectional"))
      (node (ref "R14") (pin "2") (pinfunction "2_2") (pintype "passive"))
      (node (ref "X1") (pin "8") (pinfunction "1_8") (pintype "passive"))
      (node (ref "X2") (pin "15") (pinfunction "1_15") (pintype "passive"))
    )
    (net (code "248") (name "~{RESET}") (class "Default")
      (node (ref "C8") (pin "1") (pinfunction "1_1") (pintype "passive"))
      (node (ref "IC14") (pin "29") (pinfunction "RESET_N_29") (pintype "input"))
      (node (ref "IC3") (pin "31") (pinfunction "NRST_31") (pintype "bidirectional"))
      (node (ref "IC5") (pin "4") (pinfunction "IO3_4") (pintype "bidirectional"))
      (node (ref "JP7") (pin "NO") (pinfunction "NO_NO") (pintype "passive"))
      (node (ref "R11") (pin "2") (pinfunction "2_2") (pintype "passive"))
      (node (ref "X1") (pin "6") (pinfunction "1_6") (pintype "passive"))
      (node (ref "X4") (pin "5") (pinfunction "S_5") (pintype "passive"))
    )
    (net (code "249") (name "~{USB_OTG_FS_OC}") (class "Default")
      (node (ref "IC3") (pin "146") (pinfunction "PD4_146") (pintype "bidirectional"))
      (node (ref "IC8") (pin "3") (pinfunction "~{OC}_3") (pintype "passive"))
      (node (ref "R26") (pin "1") (pinfunction "1_1") (pintype "passive"))
    )
  )
)
